# PCB-CMB-6.net
KiCad netlist of a schematic drawn in EAGLE
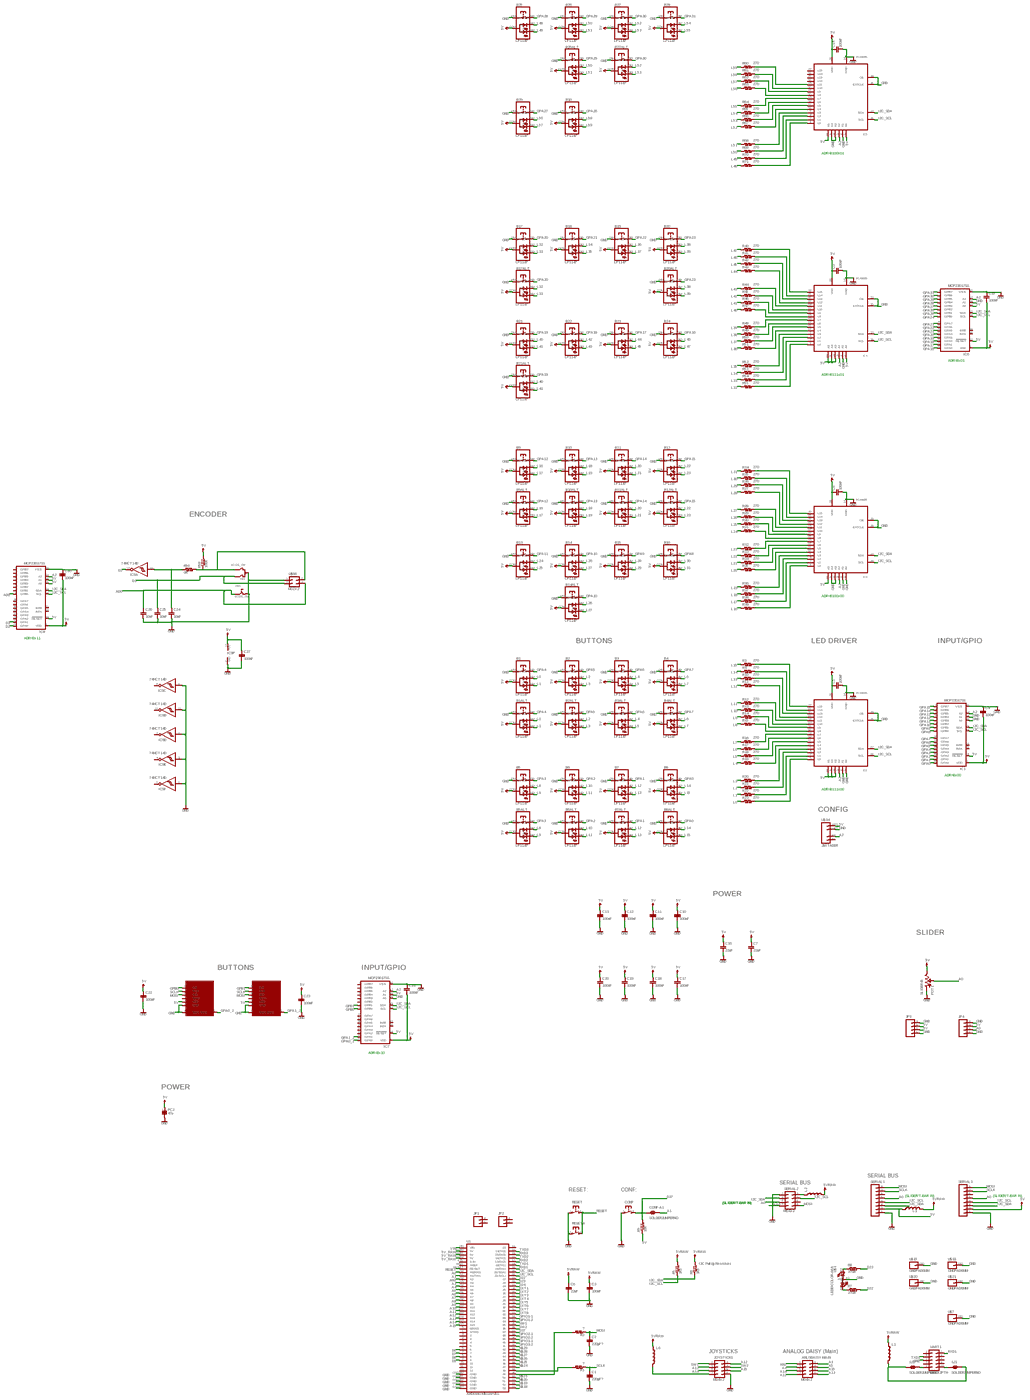
[diagram p0: schematic, sheet 1, overview]
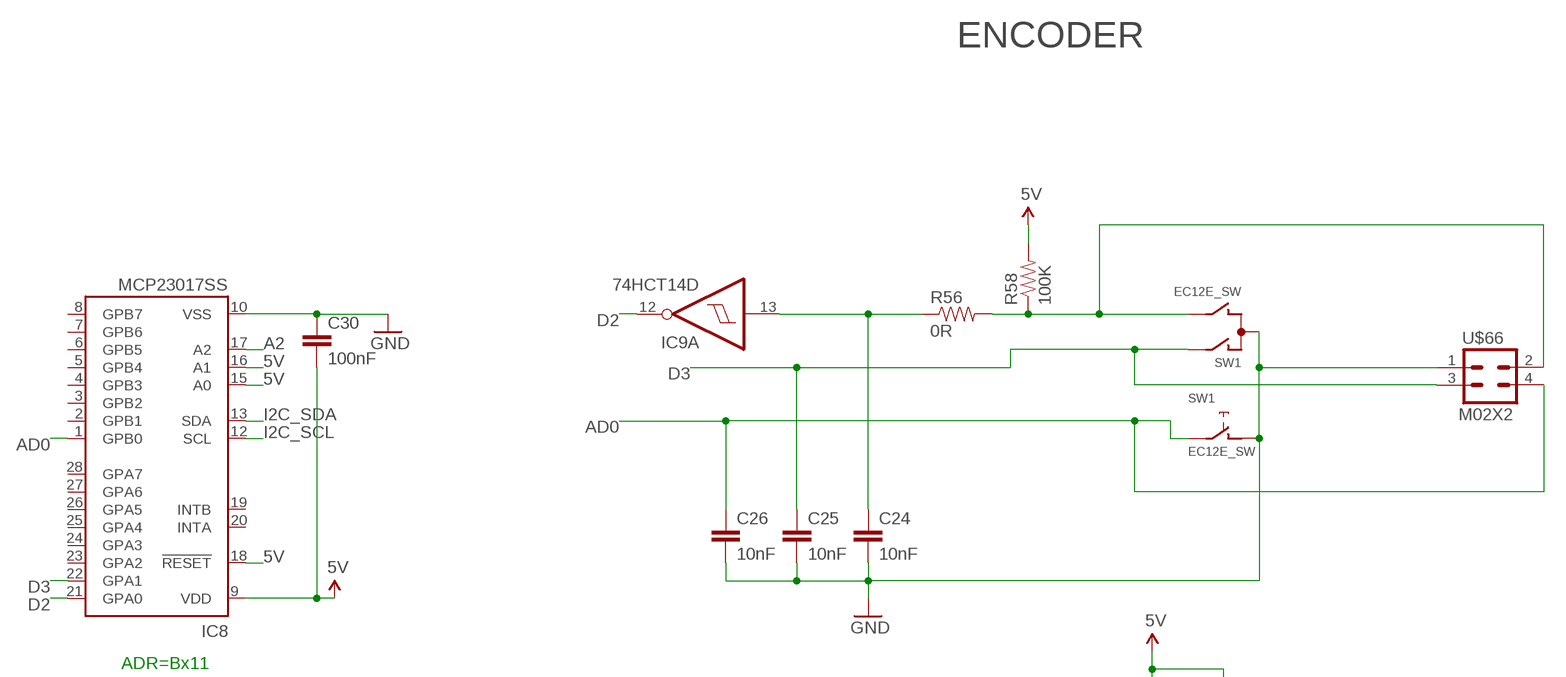
[diagram p1: schematic, sheet 1, part 1 of 6]
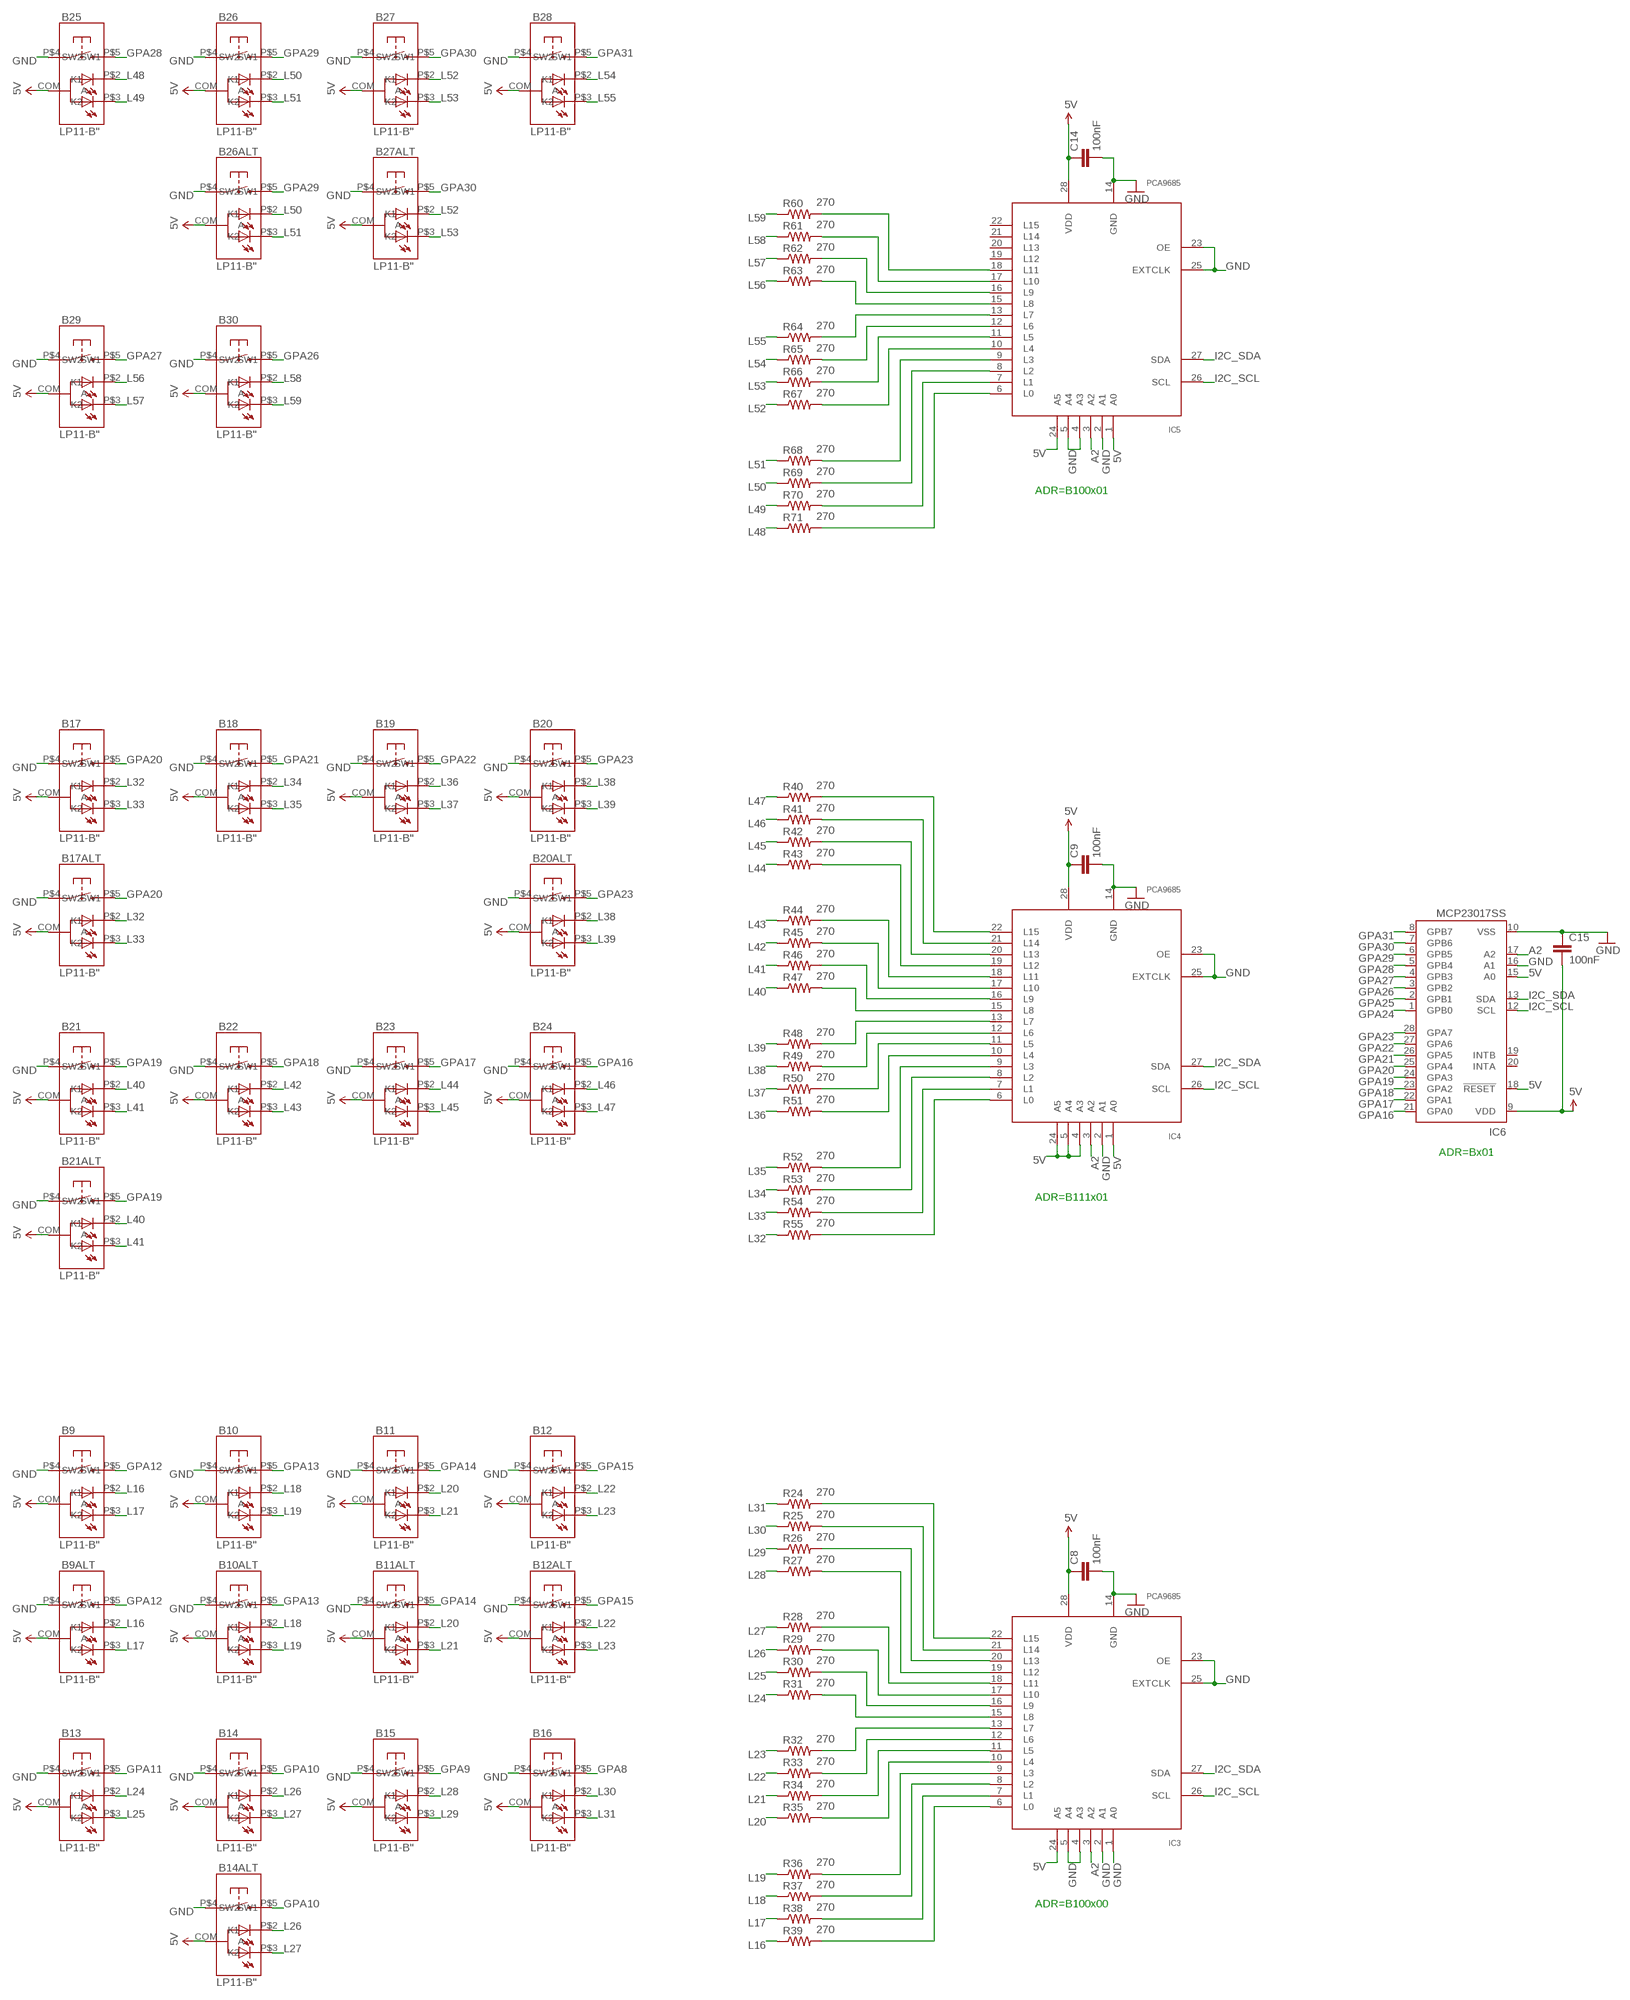
[diagram p2: schematic, sheet 1, part 2 of 6]
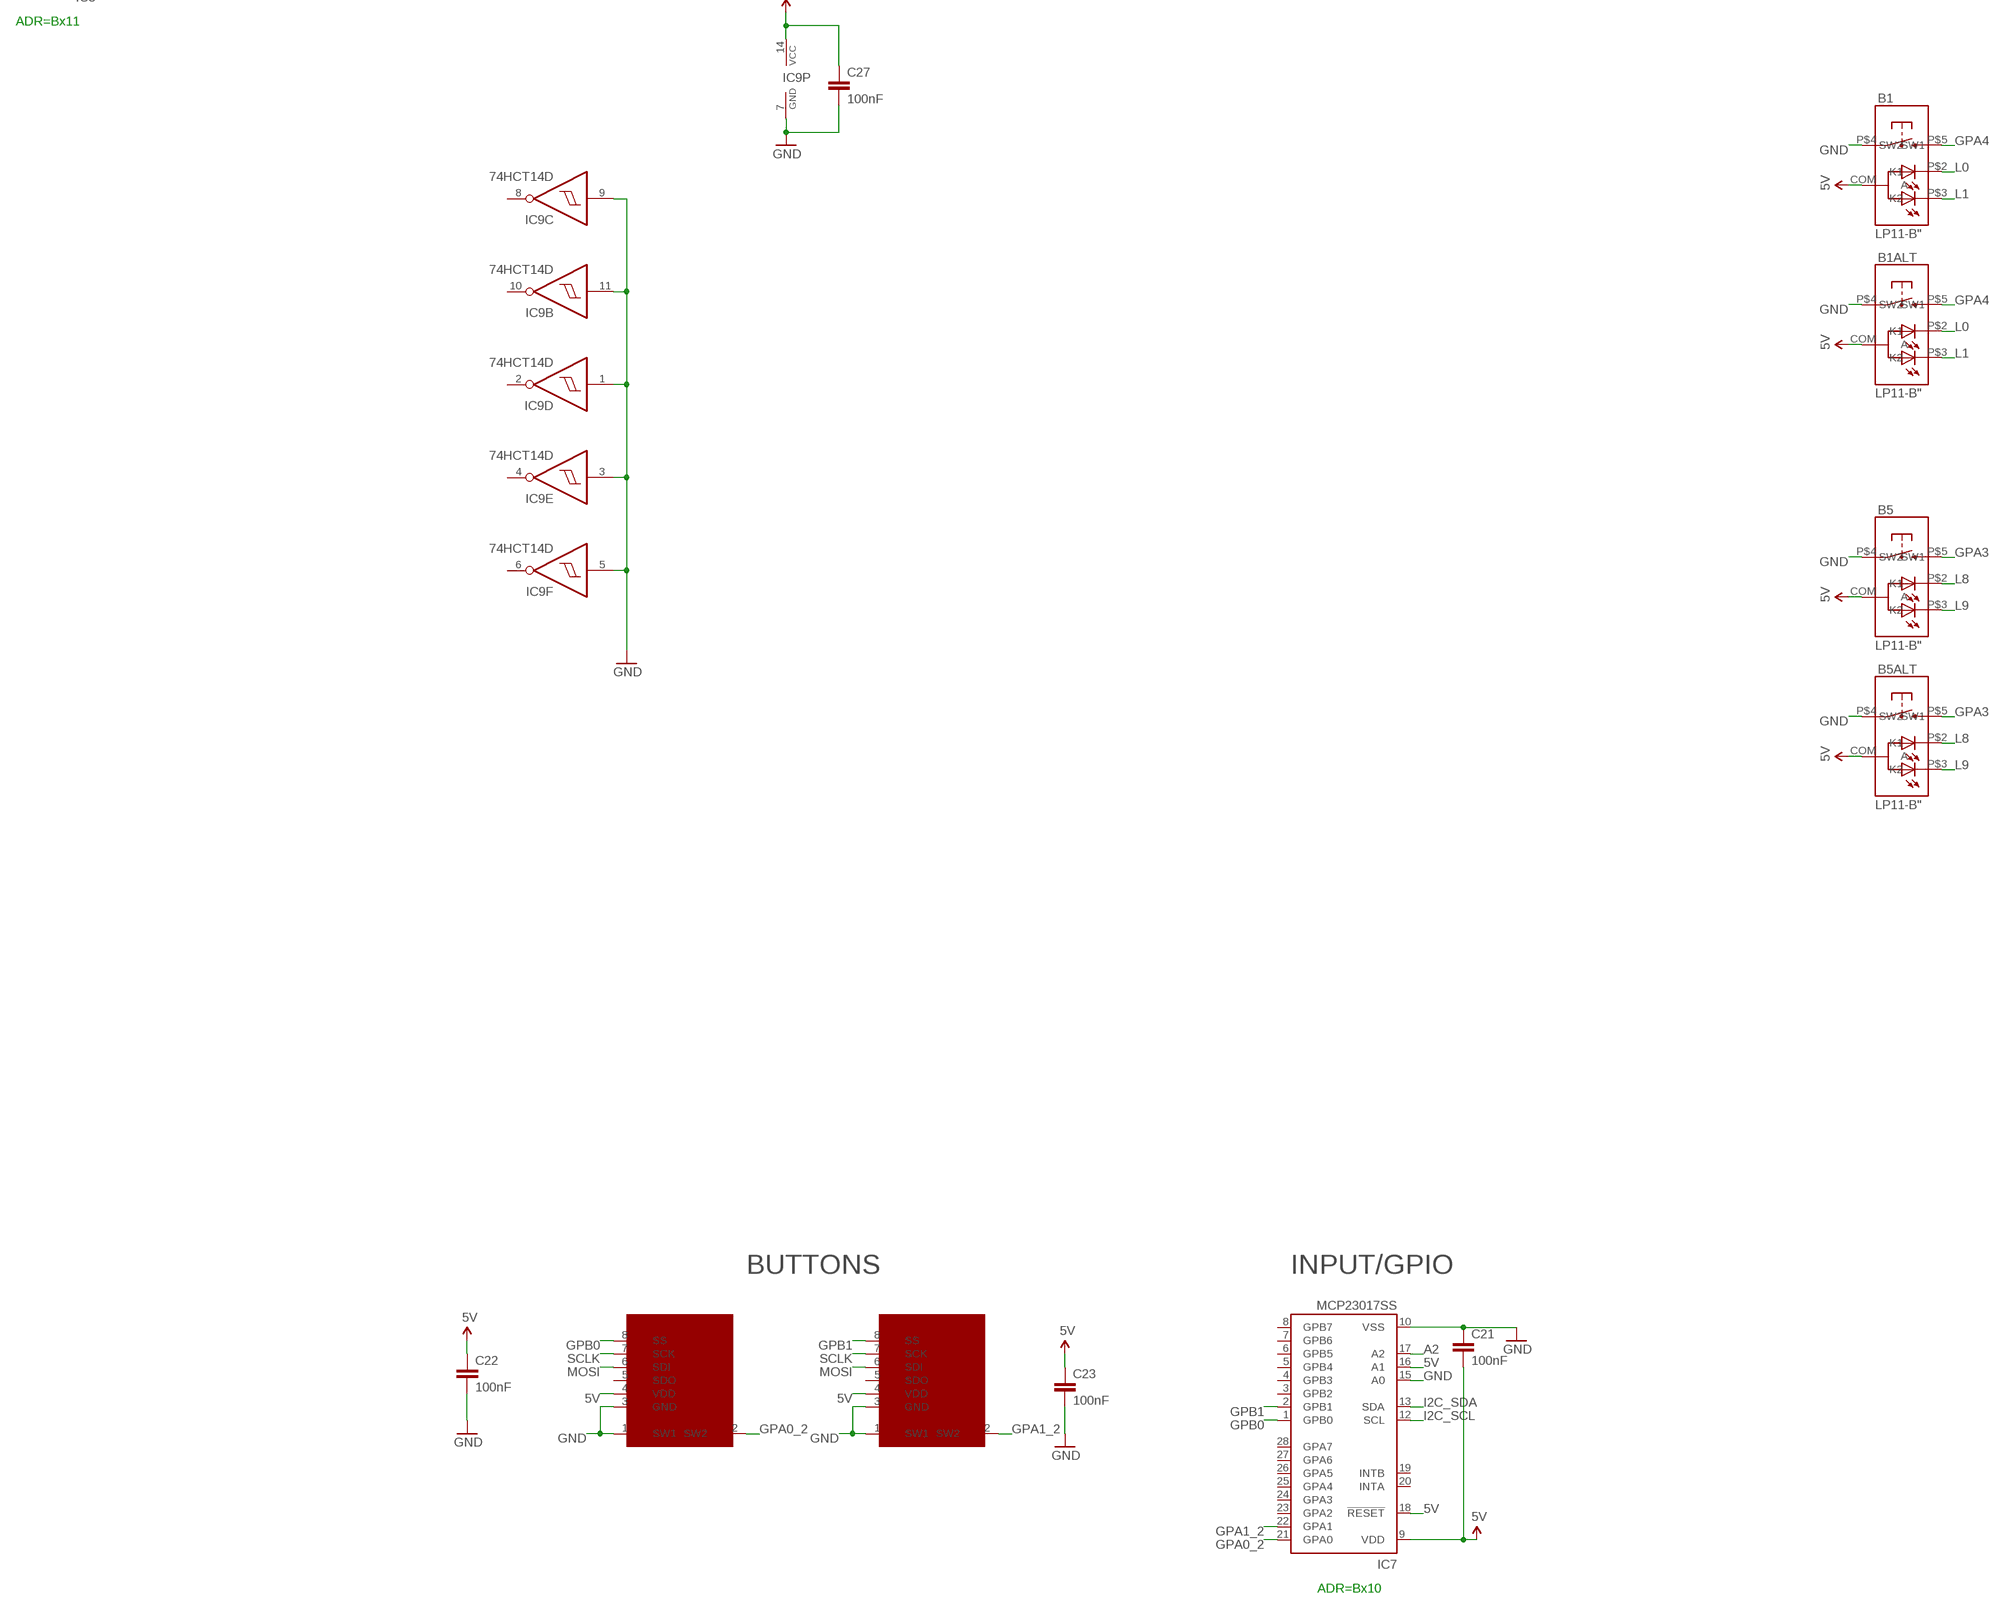
[diagram p3: schematic, sheet 1, part 3 of 6]
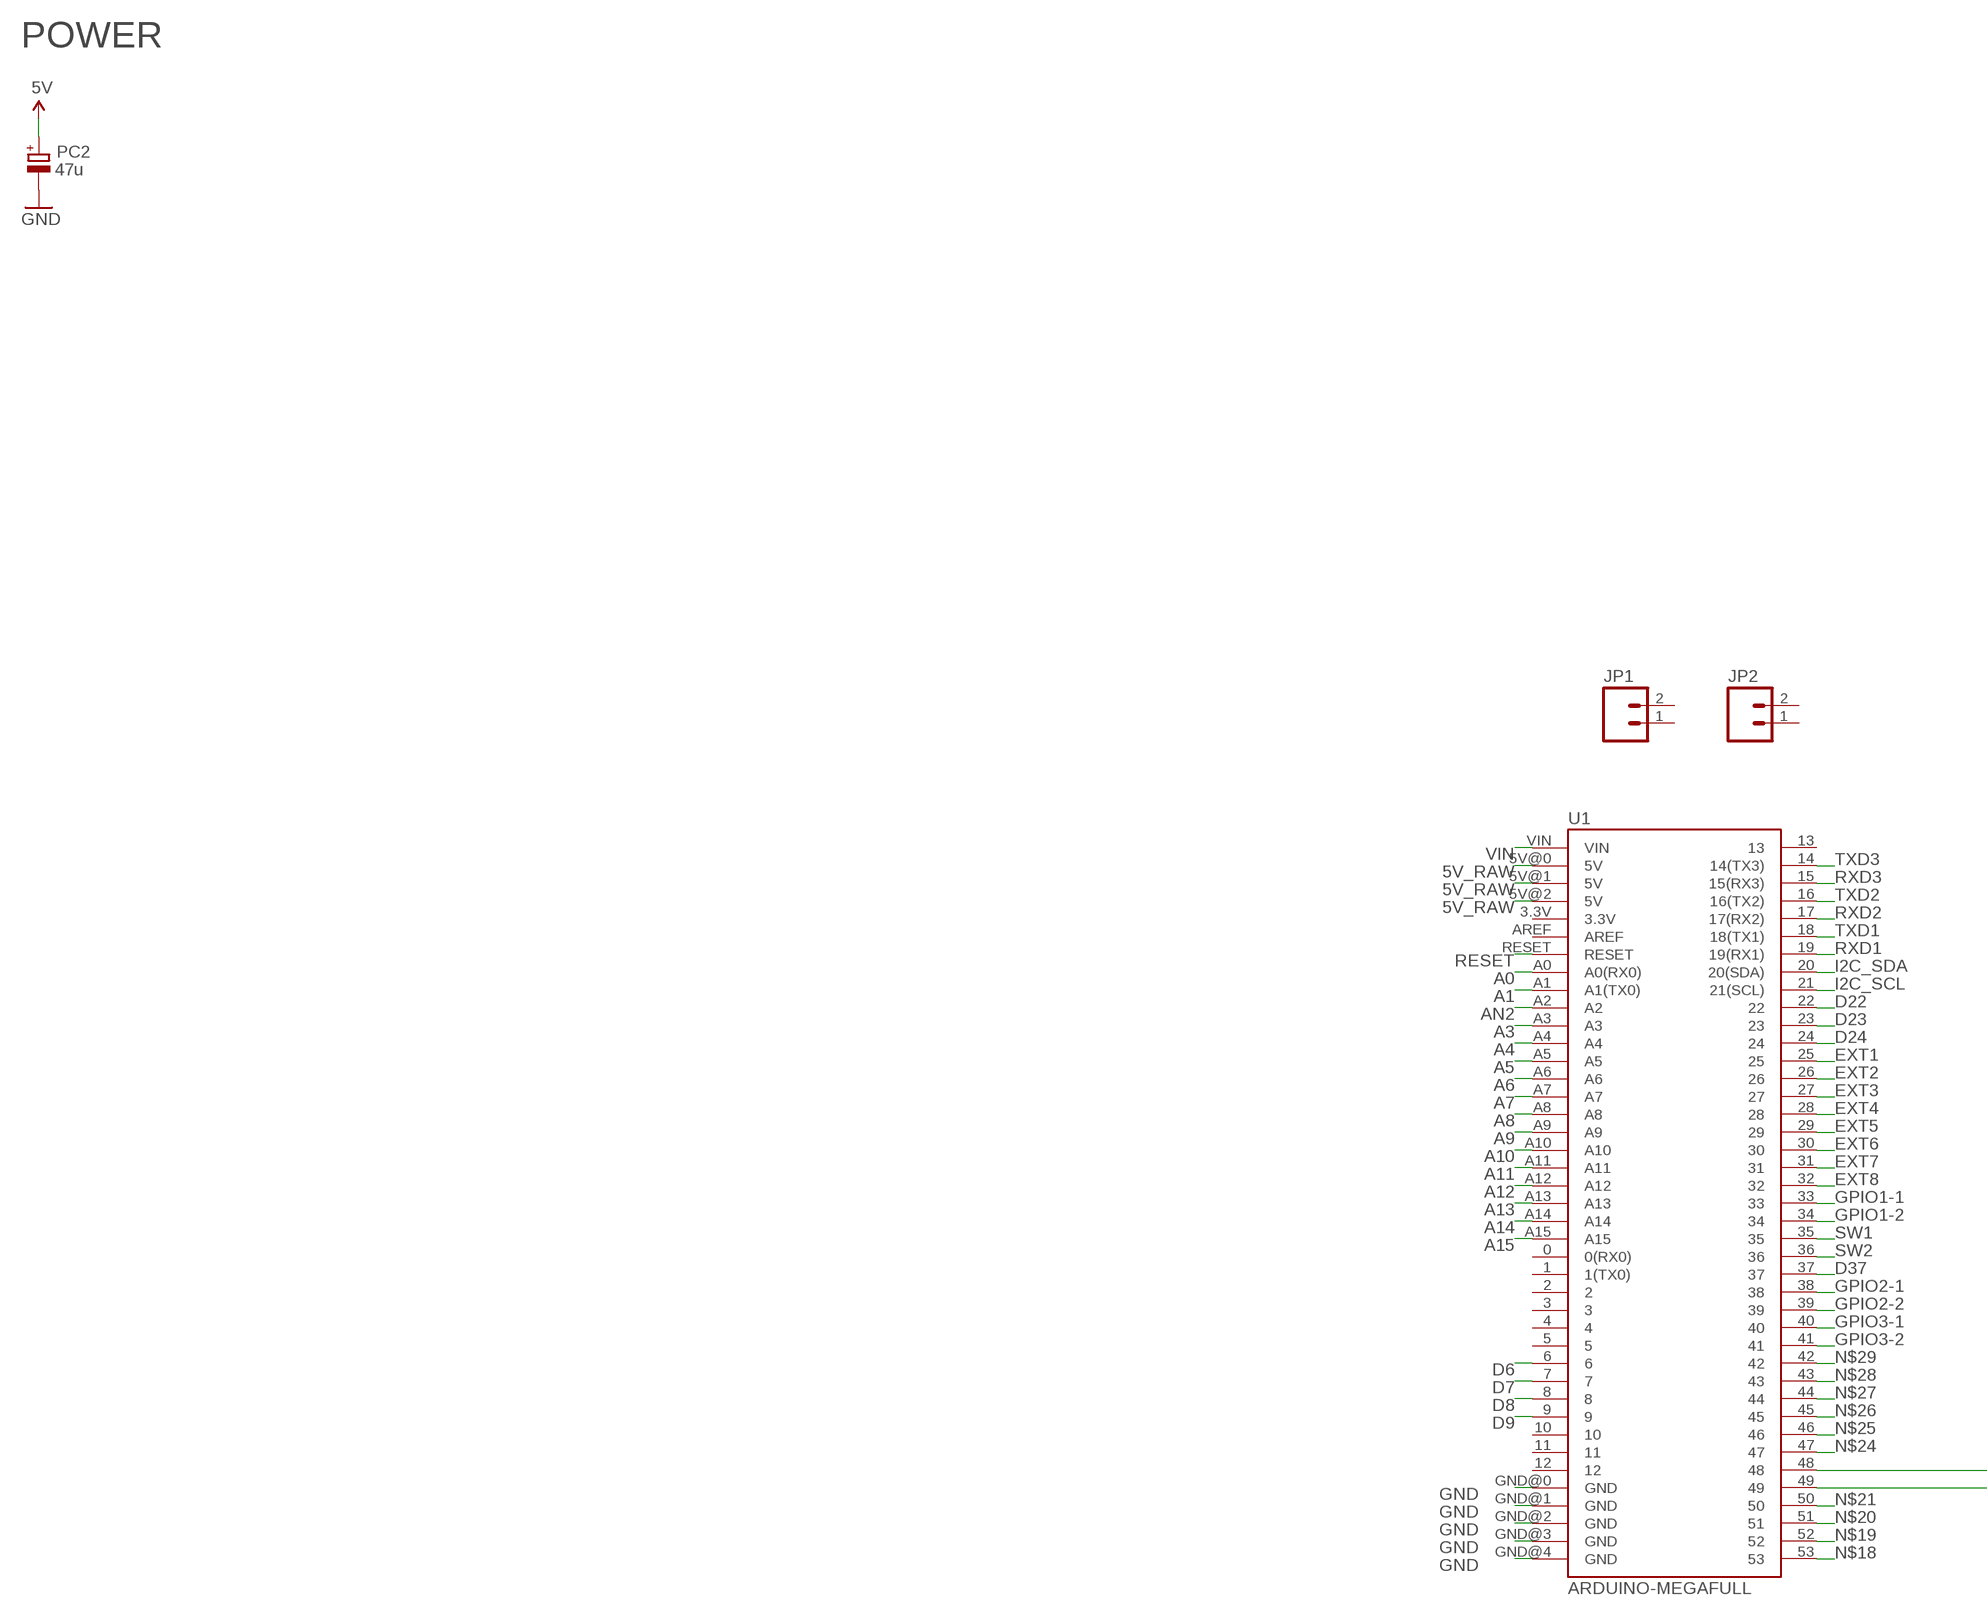
[diagram p4: schematic, sheet 1, part 4 of 6]
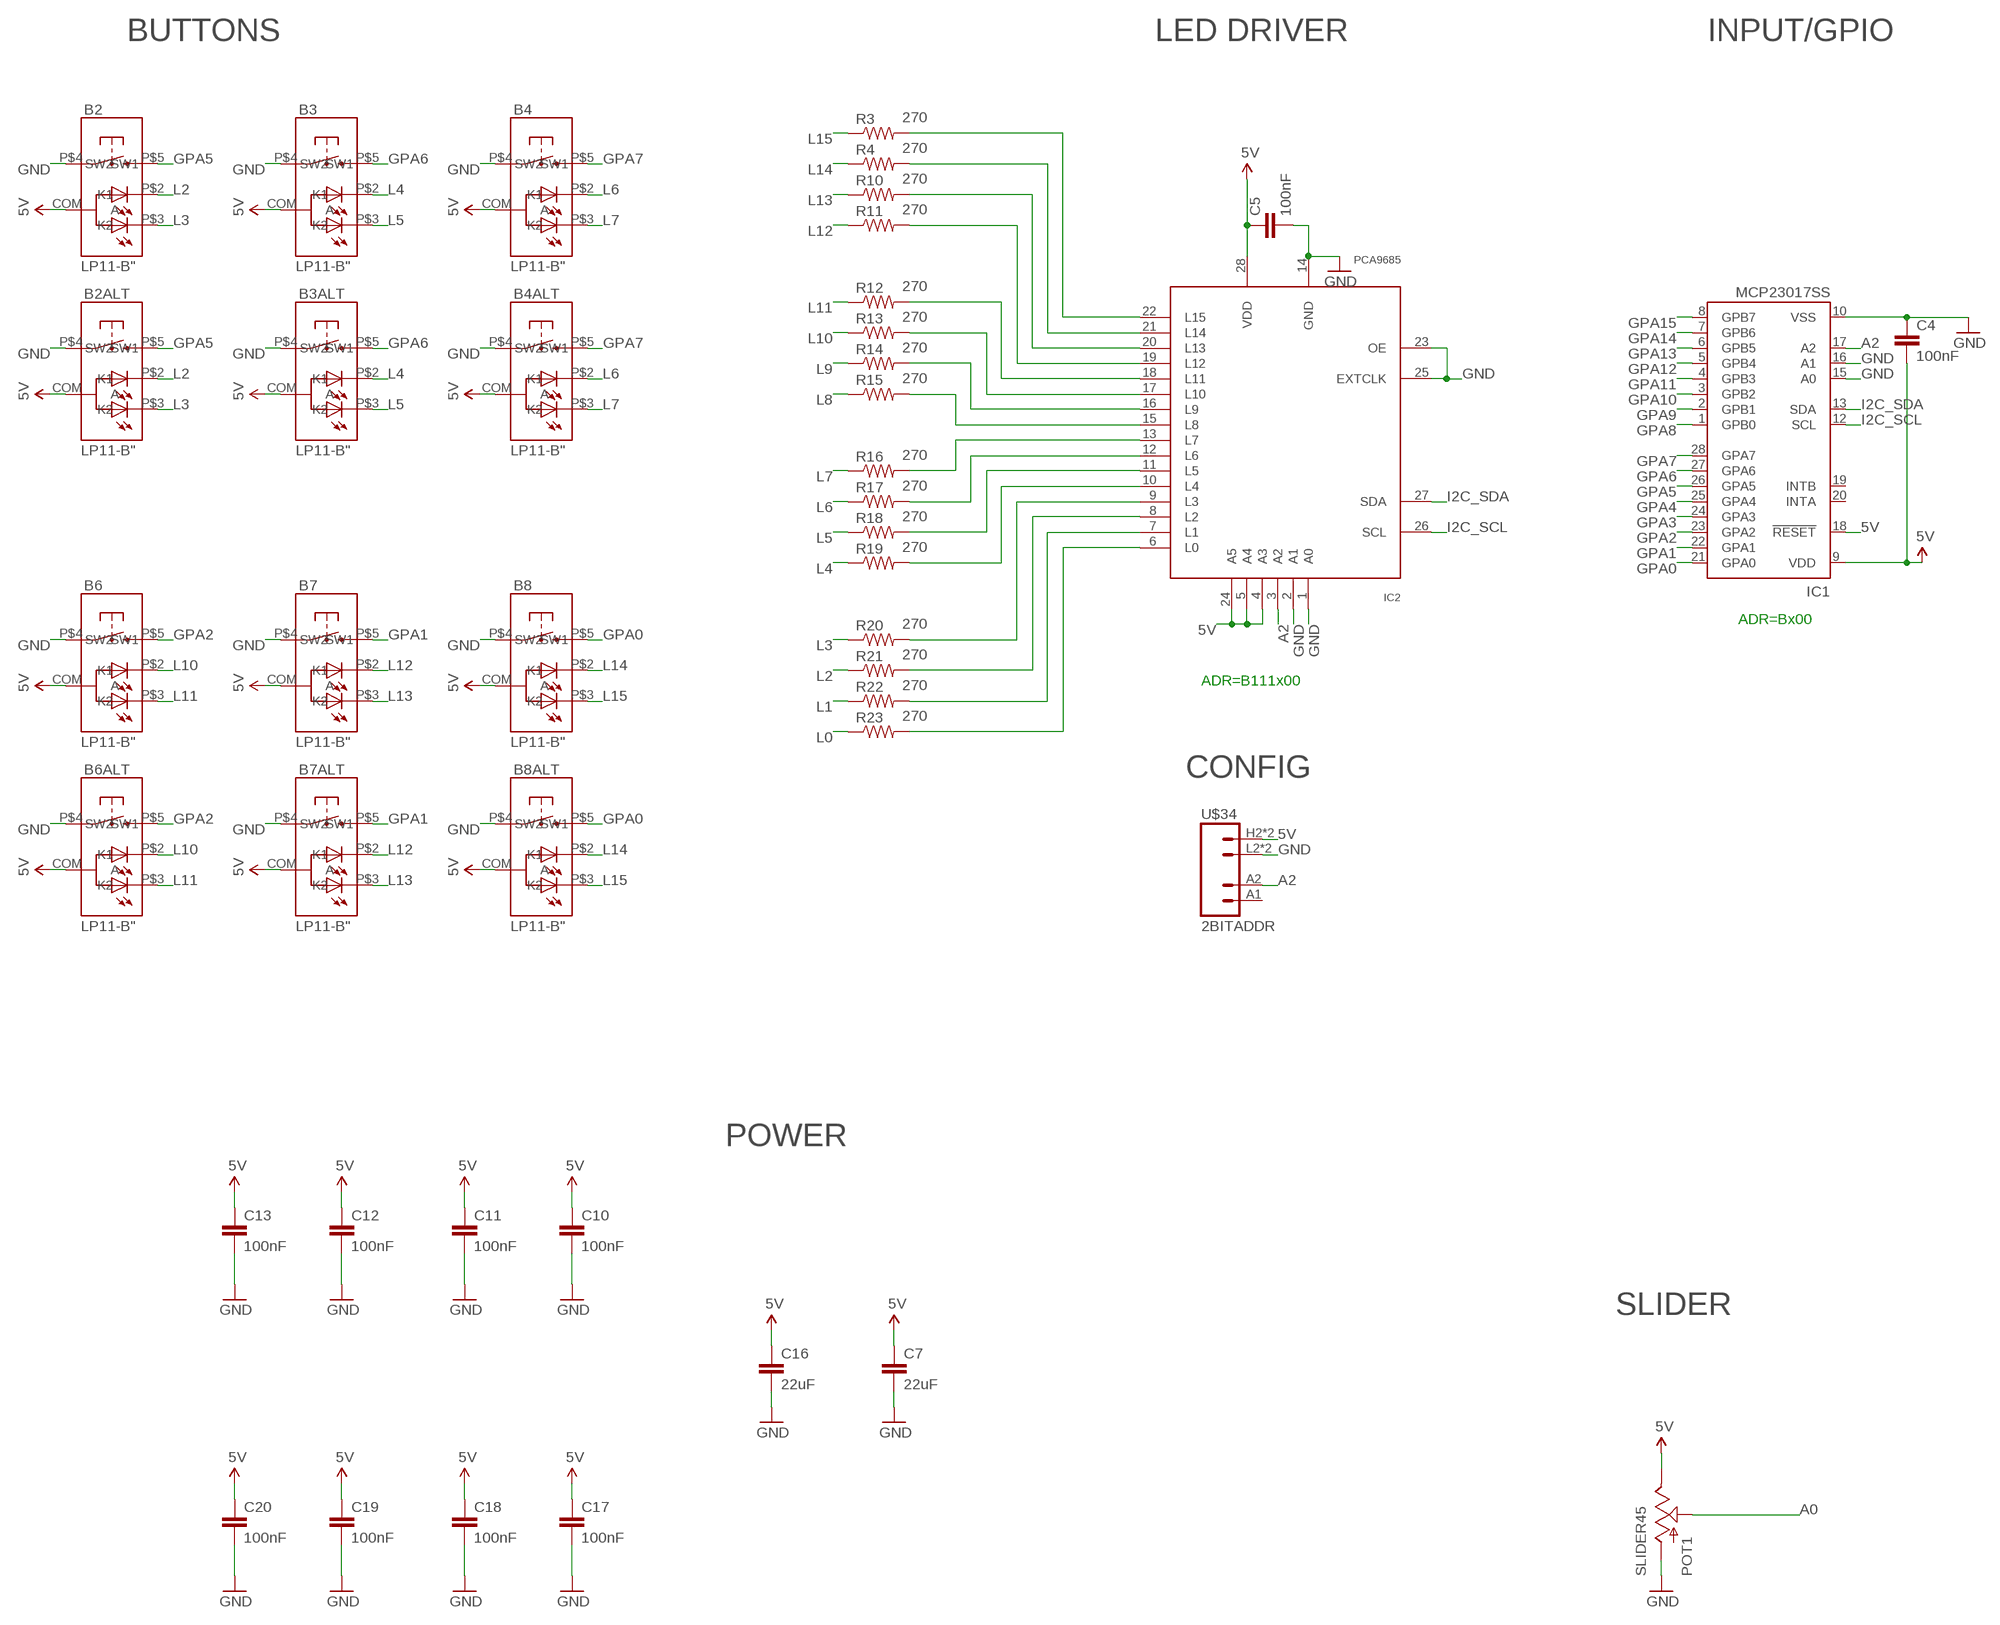
[diagram p5: schematic, sheet 1, part 5 of 6]
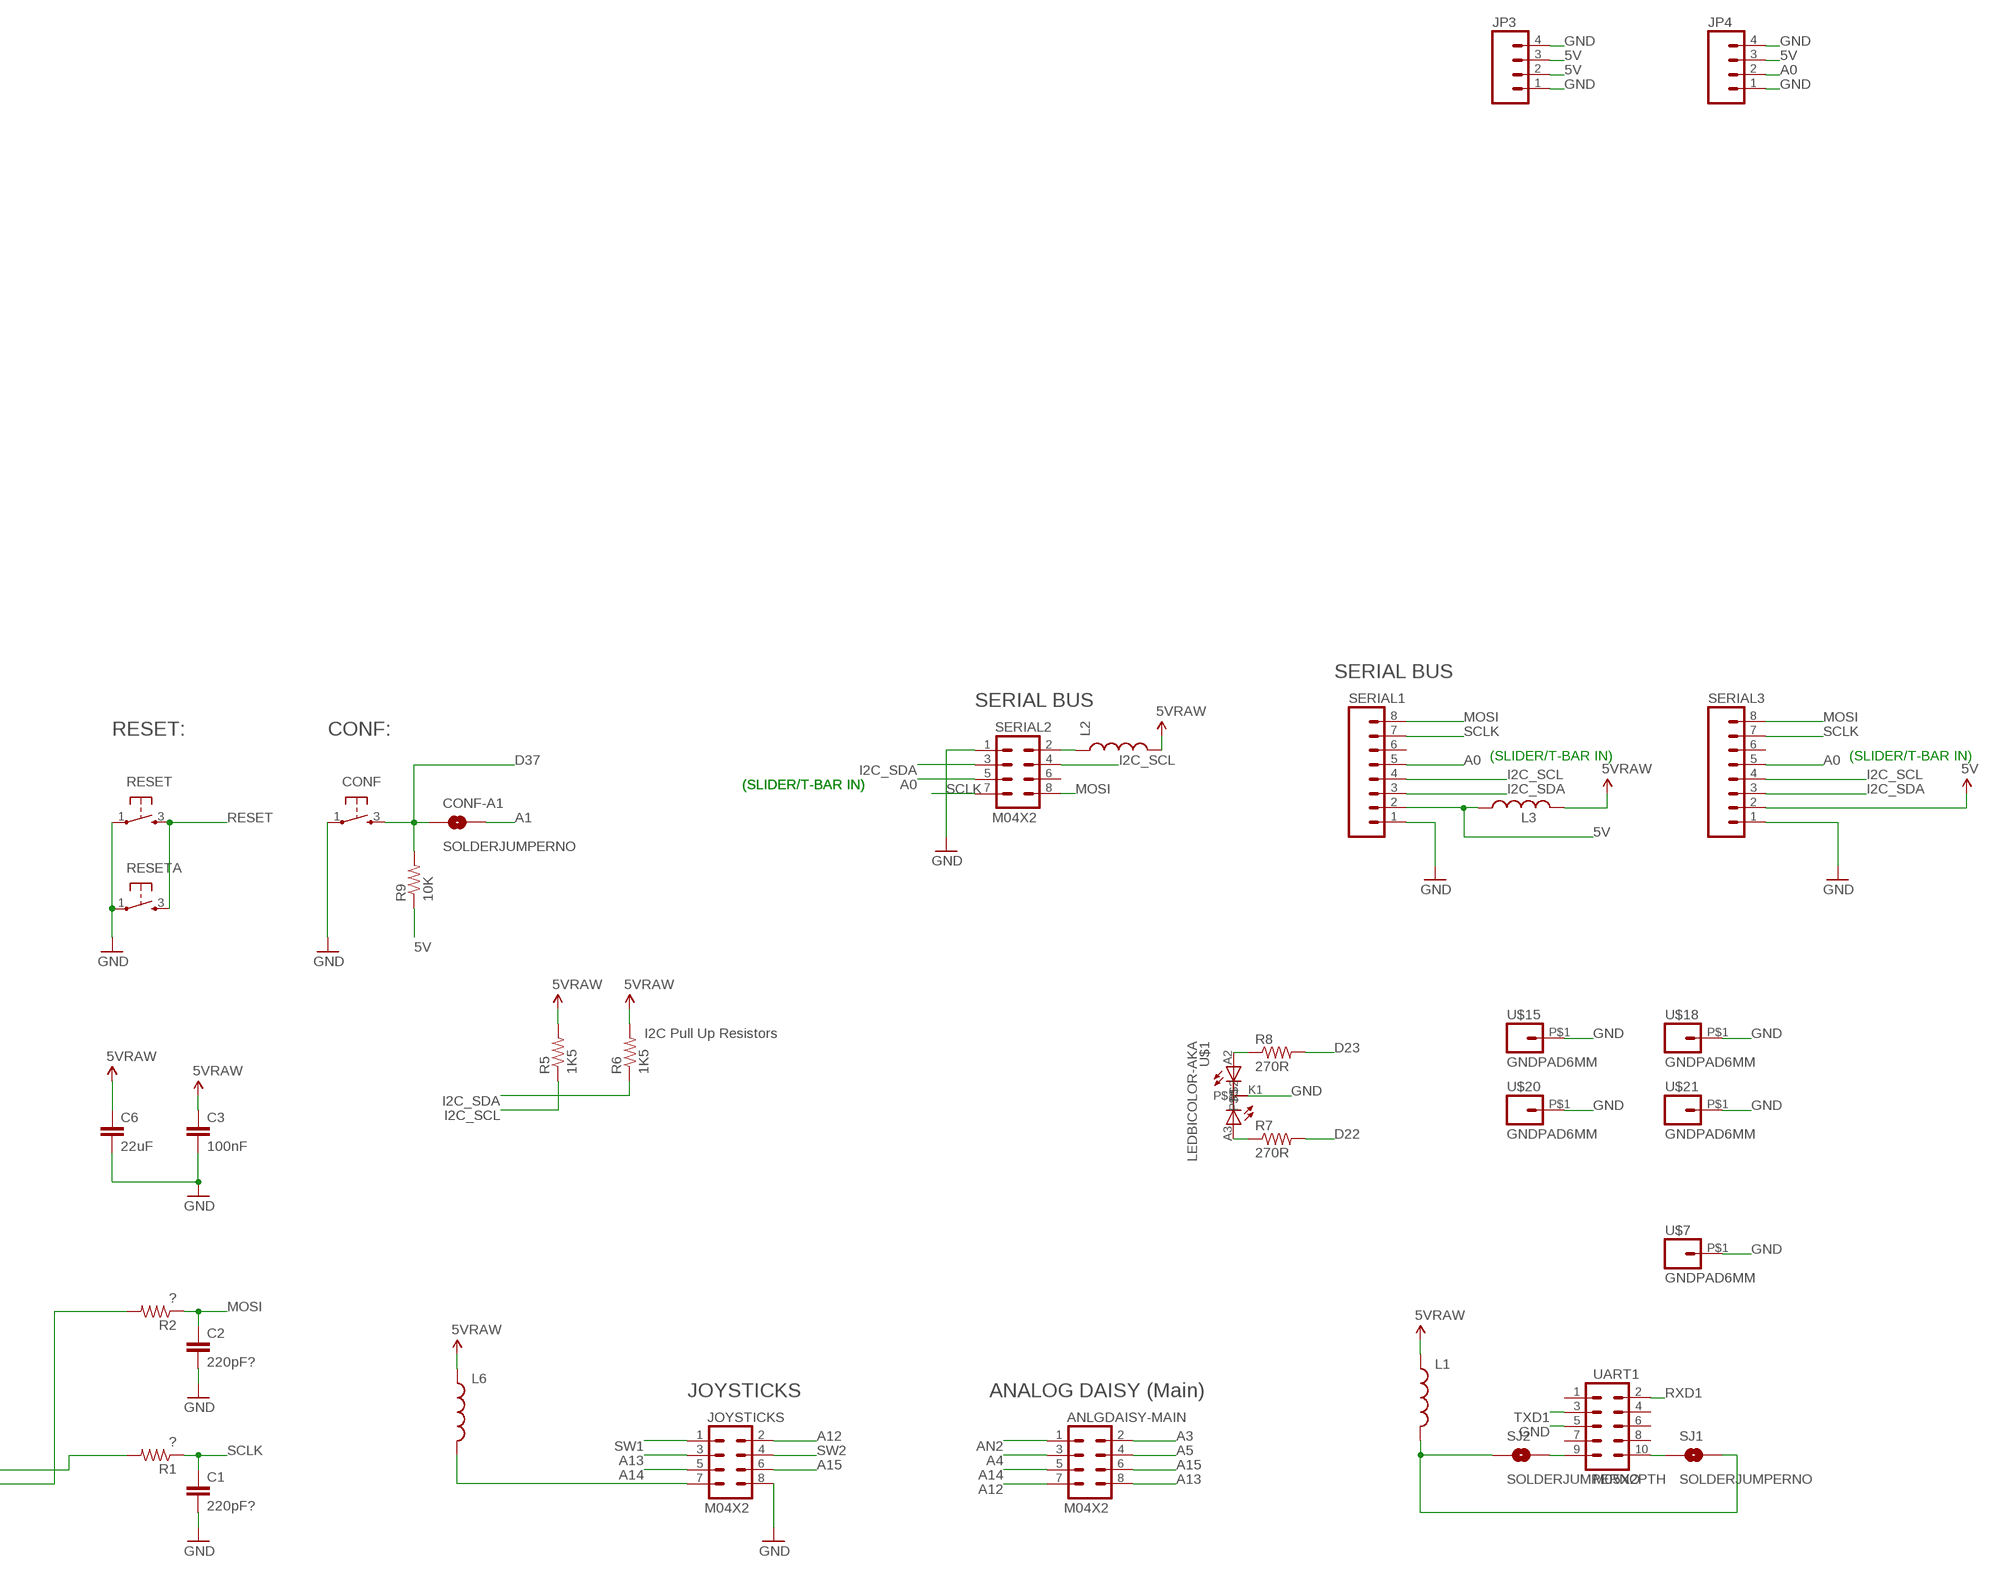
[diagram p6: schematic, sheet 1, part 6 of 6]

(export (version "E")
  (design (tool "Eeschema 10.0.6"))
  (components
    (comp (ref "ANLGDAISY-MAIN")
      (value "M04X2")
      (footprint "eagle-import:2X4")
      (libsource (lib "eagle-import") (part "M04X2"))
    )
    (comp (ref "B1")
      (value "LP11-B\"")
      (footprint "eagle-import:LP11")
      (libsource (lib "eagle-import") (part "LP11-B{dblquote}"))
    )
    (comp (ref "B1ALT")
      (value "LP11-B\"")
      (footprint "eagle-import:LP11")
      (libsource (lib "eagle-import") (part "LP11-B{dblquote}"))
    )
    (comp (ref "B2")
      (value "LP11-B\"")
      (footprint "eagle-import:LP11")
      (libsource (lib "eagle-import") (part "LP11-B{dblquote}"))
    )
    (comp (ref "B2ALT")
      (value "LP11-B\"")
      (footprint "eagle-import:LP11")
      (libsource (lib "eagle-import") (part "LP11-B{dblquote}"))
    )
    (comp (ref "B3")
      (value "LP11-B\"")
      (footprint "eagle-import:LP11")
      (libsource (lib "eagle-import") (part "LP11-B{dblquote}"))
    )
    (comp (ref "B3ALT")
      (value "LP11-B\"")
      (footprint "eagle-import:LP11")
      (libsource (lib "eagle-import") (part "LP11-B{dblquote}"))
    )
    (comp (ref "B4")
      (value "LP11-B\"")
      (footprint "eagle-import:LP11")
      (libsource (lib "eagle-import") (part "LP11-B{dblquote}"))
    )
    (comp (ref "B4ALT")
      (value "LP11-B\"")
      (footprint "eagle-import:LP11")
      (libsource (lib "eagle-import") (part "LP11-B{dblquote}"))
    )
    (comp (ref "B5")
      (value "LP11-B\"")
      (footprint "eagle-import:LP11")
      (libsource (lib "eagle-import") (part "LP11-B{dblquote}"))
    )
    (comp (ref "B5ALT")
      (value "LP11-B\"")
      (footprint "eagle-import:LP11")
      (libsource (lib "eagle-import") (part "LP11-B{dblquote}"))
    )
    (comp (ref "B6")
      (value "LP11-B\"")
      (footprint "eagle-import:LP11")
      (libsource (lib "eagle-import") (part "LP11-B{dblquote}"))
    )
    (comp (ref "B6ALT")
      (value "LP11-B\"")
      (footprint "eagle-import:LP11")
      (libsource (lib "eagle-import") (part "LP11-B{dblquote}"))
    )
    (comp (ref "B7")
      (value "LP11-B\"")
      (footprint "eagle-import:LP11")
      (libsource (lib "eagle-import") (part "LP11-B{dblquote}"))
    )
    (comp (ref "B7ALT")
      (value "LP11-B\"")
      (footprint "eagle-import:LP11")
      (libsource (lib "eagle-import") (part "LP11-B{dblquote}"))
    )
    (comp (ref "B8")
      (value "LP11-B\"")
      (footprint "eagle-import:LP11")
      (libsource (lib "eagle-import") (part "LP11-B{dblquote}"))
    )
    (comp (ref "B8ALT")
      (value "LP11-B\"")
      (footprint "eagle-import:LP11")
      (libsource (lib "eagle-import") (part "LP11-B{dblquote}"))
    )
    (comp (ref "B9")
      (value "LP11-B\"")
      (footprint "eagle-import:LP11")
      (libsource (lib "eagle-import") (part "LP11-B{dblquote}"))
    )
    (comp (ref "B9ALT")
      (value "LP11-B\"")
      (footprint "eagle-import:LP11")
      (libsource (lib "eagle-import") (part "LP11-B{dblquote}"))
    )
    (comp (ref "B10")
      (value "LP11-B\"")
      (footprint "eagle-import:LP11")
      (libsource (lib "eagle-import") (part "LP11-B{dblquote}"))
    )
    (comp (ref "B10ALT")
      (value "LP11-B\"")
      (footprint "eagle-import:LP11")
      (libsource (lib "eagle-import") (part "LP11-B{dblquote}"))
    )
    (comp (ref "B11")
      (value "LP11-B\"")
      (footprint "eagle-import:LP11")
      (libsource (lib "eagle-import") (part "LP11-B{dblquote}"))
    )
    (comp (ref "B11ALT")
      (value "LP11-B\"")
      (footprint "eagle-import:LP11")
      (libsource (lib "eagle-import") (part "LP11-B{dblquote}"))
    )
    (comp (ref "B12")
      (value "LP11-B\"")
      (footprint "eagle-import:LP11")
      (libsource (lib "eagle-import") (part "LP11-B{dblquote}"))
    )
    (comp (ref "B12ALT")
      (value "LP11-B\"")
      (footprint "eagle-import:LP11")
      (libsource (lib "eagle-import") (part "LP11-B{dblquote}"))
    )
    (comp (ref "B13")
      (value "LP11-B\"")
      (footprint "eagle-import:LP11")
      (libsource (lib "eagle-import") (part "LP11-B{dblquote}"))
    )
    (comp (ref "B14")
      (value "LP11-B\"")
      (footprint "eagle-import:LP11")
      (libsource (lib "eagle-import") (part "LP11-B{dblquote}"))
    )
    (comp (ref "B14ALT")
      (value "LP11-B\"")
      (footprint "eagle-import:LP11")
      (libsource (lib "eagle-import") (part "LP11-B{dblquote}"))
    )
    (comp (ref "B15")
      (value "LP11-B\"")
      (footprint "eagle-import:LP11")
      (libsource (lib "eagle-import") (part "LP11-B{dblquote}"))
    )
    (comp (ref "B16")
      (value "LP11-B\"")
      (footprint "eagle-import:LP11")
      (libsource (lib "eagle-import") (part "LP11-B{dblquote}"))
    )
    (comp (ref "B17")
      (value "LP11-B\"")
      (footprint "eagle-import:LP11")
      (libsource (lib "eagle-import") (part "LP11-B{dblquote}"))
    )
    (comp (ref "B17ALT")
      (value "LP11-B\"")
      (footprint "eagle-import:LP11")
      (libsource (lib "eagle-import") (part "LP11-B{dblquote}"))
    )
    (comp (ref "B18")
      (value "LP11-B\"")
      (footprint "eagle-import:LP11")
      (libsource (lib "eagle-import") (part "LP11-B{dblquote}"))
    )
    (comp (ref "B19")
      (value "LP11-B\"")
      (footprint "eagle-import:LP11")
      (libsource (lib "eagle-import") (part "LP11-B{dblquote}"))
    )
    (comp (ref "B20")
      (value "LP11-B\"")
      (footprint "eagle-import:LP11")
      (libsource (lib "eagle-import") (part "LP11-B{dblquote}"))
    )
    (comp (ref "B20ALT")
      (value "LP11-B\"")
      (footprint "eagle-import:LP11")
      (libsource (lib "eagle-import") (part "LP11-B{dblquote}"))
    )
    (comp (ref "B21")
      (value "LP11-B\"")
      (footprint "eagle-import:LP11")
      (libsource (lib "eagle-import") (part "LP11-B{dblquote}"))
    )
    (comp (ref "B21ALT")
      (value "LP11-B\"")
      (footprint "eagle-import:LP11")
      (libsource (lib "eagle-import") (part "LP11-B{dblquote}"))
    )
    (comp (ref "B22")
      (value "LP11-B\"")
      (footprint "eagle-import:LP11")
      (libsource (lib "eagle-import") (part "LP11-B{dblquote}"))
    )
    (comp (ref "B23")
      (value "LP11-B\"")
      (footprint "eagle-import:LP11")
      (libsource (lib "eagle-import") (part "LP11-B{dblquote}"))
    )
    (comp (ref "B24")
      (value "LP11-B\"")
      (footprint "eagle-import:LP11")
      (libsource (lib "eagle-import") (part "LP11-B{dblquote}"))
    )
    (comp (ref "B25")
      (value "LP11-B\"")
      (footprint "eagle-import:LP11")
      (libsource (lib "eagle-import") (part "LP11-B{dblquote}"))
    )
    (comp (ref "B26")
      (value "LP11-B\"")
      (footprint "eagle-import:LP11")
      (libsource (lib "eagle-import") (part "LP11-B{dblquote}"))
    )
    (comp (ref "B26ALT")
      (value "LP11-B\"")
      (footprint "eagle-import:LP11")
      (libsource (lib "eagle-import") (part "LP11-B{dblquote}"))
    )
    (comp (ref "B27")
      (value "LP11-B\"")
      (footprint "eagle-import:LP11")
      (libsource (lib "eagle-import") (part "LP11-B{dblquote}"))
    )
    (comp (ref "B27ALT")
      (value "LP11-B\"")
      (footprint "eagle-import:LP11")
      (libsource (lib "eagle-import") (part "LP11-B{dblquote}"))
    )
    (comp (ref "B28")
      (value "LP11-B\"")
      (footprint "eagle-import:LP11")
      (libsource (lib "eagle-import") (part "LP11-B{dblquote}"))
    )
    (comp (ref "B29")
      (value "LP11-B\"")
      (footprint "eagle-import:LP11")
      (libsource (lib "eagle-import") (part "LP11-B{dblquote}"))
    )
    (comp (ref "B30")
      (value "LP11-B\"")
      (footprint "eagle-import:LP11")
      (libsource (lib "eagle-import") (part "LP11-B{dblquote}"))
    )
    (comp (ref "C1")
      (value "220pF?")
      (footprint "eagle-import:0603-CAP")
      (libsource (lib "eagle-import") (part "CAP0603-CAP"))
    )
    (comp (ref "C2")
      (value "220pF?")
      (footprint "eagle-import:0603-CAP")
      (libsource (lib "eagle-import") (part "CAP0603-CAP"))
    )
    (comp (ref "C3")
      (value "100nF")
      (footprint "eagle-import:0603-CAP")
      (libsource (lib "eagle-import") (part "CAP0603-CAP"))
    )
    (comp (ref "C4")
      (value "100nF")
      (footprint "eagle-import:0603-CAP")
      (libsource (lib "eagle-import") (part "CAP0603-CAP"))
    )
    (comp (ref "C5")
      (value "100nF")
      (footprint "eagle-import:0603-CAP")
      (libsource (lib "eagle-import") (part "CAP0603-CAP"))
    )
    (comp (ref "C6")
      (value "22uF")
      (footprint "eagle-import:0805")
      (libsource (lib "eagle-import") (part "CAP0805"))
    )
    (comp (ref "C7")
      (value "22uF")
      (footprint "eagle-import:0805")
      (libsource (lib "eagle-import") (part "CAP0805"))
    )
    (comp (ref "C8")
      (value "100nF")
      (footprint "eagle-import:0603-CAP")
      (libsource (lib "eagle-import") (part "CAP0603-CAP"))
    )
    (comp (ref "C9")
      (value "100nF")
      (footprint "eagle-import:0603-CAP")
      (libsource (lib "eagle-import") (part "CAP0603-CAP"))
    )
    (comp (ref "C10")
      (value "100nF")
      (footprint "eagle-import:0603-CAP")
      (libsource (lib "eagle-import") (part "CAP0603-CAP"))
    )
    (comp (ref "C11")
      (value "100nF")
      (footprint "eagle-import:0603-CAP")
      (libsource (lib "eagle-import") (part "CAP0603-CAP"))
    )
    (comp (ref "C12")
      (value "100nF")
      (footprint "eagle-import:0603-CAP")
      (libsource (lib "eagle-import") (part "CAP0603-CAP"))
    )
    (comp (ref "C13")
      (value "100nF")
      (footprint "eagle-import:0603-CAP")
      (libsource (lib "eagle-import") (part "CAP0603-CAP"))
    )
    (comp (ref "C14")
      (value "100nF")
      (footprint "eagle-import:0603-CAP")
      (libsource (lib "eagle-import") (part "CAP0603-CAP"))
    )
    (comp (ref "C15")
      (value "100nF")
      (footprint "eagle-import:0603-CAP")
      (libsource (lib "eagle-import") (part "CAP0603-CAP"))
    )
    (comp (ref "C16")
      (value "22uF")
      (footprint "eagle-import:0805")
      (libsource (lib "eagle-import") (part "CAP0805"))
    )
    (comp (ref "C17")
      (value "100nF")
      (footprint "eagle-import:0603-CAP")
      (libsource (lib "eagle-import") (part "CAP0603-CAP"))
    )
    (comp (ref "C18")
      (value "100nF")
      (footprint "eagle-import:0603-CAP")
      (libsource (lib "eagle-import") (part "CAP0603-CAP"))
    )
    (comp (ref "C19")
      (value "100nF")
      (footprint "eagle-import:0603-CAP")
      (libsource (lib "eagle-import") (part "CAP0603-CAP"))
    )
    (comp (ref "C20")
      (value "100nF")
      (footprint "eagle-import:0603-CAP")
      (libsource (lib "eagle-import") (part "CAP0603-CAP"))
    )
    (comp (ref "C21")
      (value "100nF")
      (footprint "eagle-import:0603-CAP")
      (libsource (lib "eagle-import") (part "CAP0603-CAP"))
    )
    (comp (ref "C22")
      (value "100nF")
      (footprint "eagle-import:0603-CAP")
      (libsource (lib "eagle-import") (part "CAP0603-CAP"))
    )
    (comp (ref "C23")
      (value "100nF")
      (footprint "eagle-import:0603-CAP")
      (libsource (lib "eagle-import") (part "CAP0603-CAP"))
    )
    (comp (ref "C24")
      (value "10nF")
      (footprint "eagle-import:0603-CAP")
      (libsource (lib "eagle-import") (part "CAP0603-CAP"))
    )
    (comp (ref "C25")
      (value "10nF")
      (footprint "eagle-import:0603-CAP")
      (libsource (lib "eagle-import") (part "CAP0603-CAP"))
    )
    (comp (ref "C26")
      (value "10nF")
      (footprint "eagle-import:0603-CAP")
      (libsource (lib "eagle-import") (part "CAP0603-CAP"))
    )
    (comp (ref "C27")
      (value "100nF")
      (footprint "eagle-import:0603-CAP")
      (libsource (lib "eagle-import") (part "CAP0603-CAP"))
    )
    (comp (ref "C30")
      (value "100nF")
      (footprint "eagle-import:0603-CAP")
      (libsource (lib "eagle-import") (part "CAP0603-CAP"))
    )
    (comp (ref "CONF")
      (value "TAC_SWITCH")
      (footprint "eagle-import:PUSHBUTTON")
      (libsource (lib "eagle-import") (part "TAC_SWITCH"))
    )
    (comp (ref "CONF-A1")
      (value "SOLDERJUMPERNO")
      (footprint "eagle-import:SJ_2S-NO")
      (libsource (lib "eagle-import") (part "SOLDERJUMPERNO"))
    )
    (comp (ref "IC1")
      (value "MCP23017SS")
      (footprint "eagle-import:SSOP28")
      (fields
        (field (name "MF") "MICROCHIP")
        (field (name "MPN") "MCP23017-E/SS")
        (field (name "MPN_1") "MCP23017-E/SS")
        (field (name "OC_FARNELL") "1467674")
        (field (name "OC_NEWARK") "31K2960")
      )
      (libsource (lib "eagle-import") (part "MCP23017SS"))
    )
    (comp (ref "IC2")
      (value "PCA9685")
      (footprint "eagle-import:TSSOP28")
      (libsource (lib "eagle-import") (part "PCA9685"))
    )
    (comp (ref "IC3")
      (value "PCA9685")
      (footprint "eagle-import:TSSOP28")
      (libsource (lib "eagle-import") (part "PCA9685"))
    )
    (comp (ref "IC4")
      (value "PCA9685")
      (footprint "eagle-import:TSSOP28")
      (libsource (lib "eagle-import") (part "PCA9685"))
    )
    (comp (ref "IC5")
      (value "PCA9685")
      (footprint "eagle-import:TSSOP28")
      (libsource (lib "eagle-import") (part "PCA9685"))
    )
    (comp (ref "IC6")
      (value "MCP23017SS")
      (footprint "eagle-import:SSOP28")
      (fields
        (field (name "MF") "MICROCHIP")
        (field (name "MPN") "MCP23017-E/SS")
        (field (name "MPN_1") "MCP23017-E/SS")
        (field (name "OC_FARNELL") "1467674")
        (field (name "OC_NEWARK") "31K2960")
      )
      (libsource (lib "eagle-import") (part "MCP23017SS"))
    )
    (comp (ref "IC7")
      (value "MCP23017SS")
      (footprint "eagle-import:SSOP28")
      (fields
        (field (name "MF") "MICROCHIP")
        (field (name "MPN") "MCP23017-E/SS")
        (field (name "MPN_1") "MCP23017-E/SS")
        (field (name "OC_FARNELL") "1467674")
        (field (name "OC_NEWARK") "31K2960")
      )
      (libsource (lib "eagle-import") (part "MCP23017SS"))
    )
    (comp (ref "IC8")
      (value "MCP23017SS")
      (footprint "eagle-import:SSOP28")
      (fields
        (field (name "MF") "MICROCHIP")
        (field (name "MPN") "MCP23017-E/SS")
        (field (name "MPN_1") "MCP23017-E/SS")
        (field (name "OC_FARNELL") "1467674")
        (field (name "OC_NEWARK") "31K2960")
      )
      (libsource (lib "eagle-import") (part "MCP23017SS"))
    )
    (comp (ref "IC9")
      (value "74HCT14D")
      (footprint "eagle-import:SO14")
      (libsource (lib "eagle-import") (part "7414DHCT"))
    )
    (comp (ref "JOYSTICKS")
      (value "M04X2")
      (footprint "eagle-import:2X4")
      (libsource (lib "eagle-import") (part "M04X2"))
    )
    (comp (ref "JP1")
      (value "M02PTH")
      (footprint "eagle-import:1X02")
      (libsource (lib "eagle-import") (part "M02PTH"))
    )
    (comp (ref "JP2")
      (value "M02PTH")
      (footprint "eagle-import:1X02")
      (libsource (lib "eagle-import") (part "M02PTH"))
    )
    (comp (ref "JP3")
      (value "M04PTH")
      (footprint "eagle-import:1X04")
      (libsource (lib "eagle-import") (part "M04PTH"))
    )
    (comp (ref "JP4")
      (value "M04PTH")
      (footprint "eagle-import:1X04")
      (libsource (lib "eagle-import") (part "M04PTH"))
    )
    (comp (ref "L1")
      (value "INDUCTOR0805")
      (footprint "eagle-import:0805")
      (libsource (lib "eagle-import") (part "INDUCTOR0805"))
    )
    (comp (ref "L2")
      (value "INDUCTOR0805")
      (footprint "eagle-import:0805")
      (libsource (lib "eagle-import") (part "INDUCTOR0805"))
    )
    (comp (ref "L3")
      (value "INDUCTOR0805")
      (footprint "eagle-import:0805")
      (libsource (lib "eagle-import") (part "INDUCTOR0805"))
    )
    (comp (ref "L6")
      (value "INDUCTOR0805")
      (footprint "eagle-import:0805")
      (libsource (lib "eagle-import") (part "INDUCTOR0805"))
    )
    (comp (ref "PC2")
      (value "47u")
      (footprint "eagle-import:PANASONIC_D")
      (libsource (lib "eagle-import") (part "CPOL-EUD"))
    )
    (comp (ref "POT1")
      (value "SLIDER45")
      (footprint "eagle-import:SLIDER45")
      (libsource (lib "eagle-import") (part "SLIDER45"))
    )
    (comp (ref "R1")
      (value "?")
      (footprint "eagle-import:0603-RES")
      (libsource (lib "eagle-import") (part "RESISTOR0603-RES"))
    )
    (comp (ref "R2")
      (value "?")
      (footprint "eagle-import:0603-RES")
      (libsource (lib "eagle-import") (part "RESISTOR0603-RES"))
    )
    (comp (ref "R3")
      (value "270")
      (footprint "eagle-import:0603-RES")
      (libsource (lib "eagle-import") (part "RESISTOR0603-RES"))
    )
    (comp (ref "R4")
      (value "270")
      (footprint "eagle-import:0603-RES")
      (libsource (lib "eagle-import") (part "RESISTOR0603-RES"))
    )
    (comp (ref "R5")
      (value "1K5")
      (footprint "eagle-import:0603-RES")
      (libsource (lib "eagle-import") (part "RESISTOR0603-RES"))
    )
    (comp (ref "R6")
      (value "1K5")
      (footprint "eagle-import:0603-RES")
      (libsource (lib "eagle-import") (part "RESISTOR0603-RES"))
    )
    (comp (ref "R7")
      (value "270R")
      (footprint "eagle-import:0603-RES")
      (libsource (lib "eagle-import") (part "RESISTOR0603-RES"))
    )
    (comp (ref "R8")
      (value "270R")
      (footprint "eagle-import:0603-RES")
      (libsource (lib "eagle-import") (part "RESISTOR0603-RES"))
    )
    (comp (ref "R9")
      (value "10K")
      (footprint "eagle-import:0603-RES")
      (libsource (lib "eagle-import") (part "RESISTOR0603-RES"))
    )
    (comp (ref "R10")
      (value "270")
      (footprint "eagle-import:0603-RES")
      (libsource (lib "eagle-import") (part "RESISTOR0603-RES"))
    )
    (comp (ref "R11")
      (value "270")
      (footprint "eagle-import:0603-RES")
      (libsource (lib "eagle-import") (part "RESISTOR0603-RES"))
    )
    (comp (ref "R12")
      (value "270")
      (footprint "eagle-import:0603-RES")
      (libsource (lib "eagle-import") (part "RESISTOR0603-RES"))
    )
    (comp (ref "R13")
      (value "270")
      (footprint "eagle-import:0603-RES")
      (libsource (lib "eagle-import") (part "RESISTOR0603-RES"))
    )
    (comp (ref "R14")
      (value "270")
      (footprint "eagle-import:0603-RES")
      (libsource (lib "eagle-import") (part "RESISTOR0603-RES"))
    )
    (comp (ref "R15")
      (value "270")
      (footprint "eagle-import:0603-RES")
      (libsource (lib "eagle-import") (part "RESISTOR0603-RES"))
    )
    (comp (ref "R16")
      (value "270")
      (footprint "eagle-import:0603-RES")
      (libsource (lib "eagle-import") (part "RESISTOR0603-RES"))
    )
    (comp (ref "R17")
      (value "270")
      (footprint "eagle-import:0603-RES")
      (libsource (lib "eagle-import") (part "RESISTOR0603-RES"))
    )
    (comp (ref "R18")
      (value "270")
      (footprint "eagle-import:0603-RES")
      (libsource (lib "eagle-import") (part "RESISTOR0603-RES"))
    )
    (comp (ref "R19")
      (value "270")
      (footprint "eagle-import:0603-RES")
      (libsource (lib "eagle-import") (part "RESISTOR0603-RES"))
    )
    (comp (ref "R20")
      (value "270")
      (footprint "eagle-import:0603-RES")
      (libsource (lib "eagle-import") (part "RESISTOR0603-RES"))
    )
    (comp (ref "R21")
      (value "270")
      (footprint "eagle-import:0603-RES")
      (libsource (lib "eagle-import") (part "RESISTOR0603-RES"))
    )
    (comp (ref "R22")
      (value "270")
      (footprint "eagle-import:0603-RES")
      (libsource (lib "eagle-import") (part "RESISTOR0603-RES"))
    )
    (comp (ref "R23")
      (value "270")
      (footprint "eagle-import:0603-RES")
      (libsource (lib "eagle-import") (part "RESISTOR0603-RES"))
    )
    (comp (ref "R24")
      (value "270")
      (footprint "eagle-import:0603-RES")
      (libsource (lib "eagle-import") (part "RESISTOR0603-RES"))
    )
    (comp (ref "R25")
      (value "270")
      (footprint "eagle-import:0603-RES")
      (libsource (lib "eagle-import") (part "RESISTOR0603-RES"))
    )
    (comp (ref "R26")
      (value "270")
      (footprint "eagle-import:0603-RES")
      (libsource (lib "eagle-import") (part "RESISTOR0603-RES"))
    )
    (comp (ref "R27")
      (value "270")
      (footprint "eagle-import:0603-RES")
      (libsource (lib "eagle-import") (part "RESISTOR0603-RES"))
    )
    (comp (ref "R28")
      (value "270")
      (footprint "eagle-import:0603-RES")
      (libsource (lib "eagle-import") (part "RESISTOR0603-RES"))
    )
    (comp (ref "R29")
      (value "270")
      (footprint "eagle-import:0603-RES")
      (libsource (lib "eagle-import") (part "RESISTOR0603-RES"))
    )
    (comp (ref "R30")
      (value "270")
      (footprint "eagle-import:0603-RES")
      (libsource (lib "eagle-import") (part "RESISTOR0603-RES"))
    )
    (comp (ref "R31")
      (value "270")
      (footprint "eagle-import:0603-RES")
      (libsource (lib "eagle-import") (part "RESISTOR0603-RES"))
    )
    (comp (ref "R32")
      (value "270")
      (footprint "eagle-import:0603-RES")
      (libsource (lib "eagle-import") (part "RESISTOR0603-RES"))
    )
    (comp (ref "R33")
      (value "270")
      (footprint "eagle-import:0603-RES")
      (libsource (lib "eagle-import") (part "RESISTOR0603-RES"))
    )
    (comp (ref "R34")
      (value "270")
      (footprint "eagle-import:0603-RES")
      (libsource (lib "eagle-import") (part "RESISTOR0603-RES"))
    )
    (comp (ref "R35")
      (value "270")
      (footprint "eagle-import:0603-RES")
      (libsource (lib "eagle-import") (part "RESISTOR0603-RES"))
    )
    (comp (ref "R36")
      (value "270")
      (footprint "eagle-import:0603-RES")
      (libsource (lib "eagle-import") (part "RESISTOR0603-RES"))
    )
    (comp (ref "R37")
      (value "270")
      (footprint "eagle-import:0603-RES")
      (libsource (lib "eagle-import") (part "RESISTOR0603-RES"))
    )
    (comp (ref "R38")
      (value "270")
      (footprint "eagle-import:0603-RES")
      (libsource (lib "eagle-import") (part "RESISTOR0603-RES"))
    )
    (comp (ref "R39")
      (value "270")
      (footprint "eagle-import:0603-RES")
      (libsource (lib "eagle-import") (part "RESISTOR0603-RES"))
    )
    (comp (ref "R40")
      (value "270")
      (footprint "eagle-import:0603-RES")
      (libsource (lib "eagle-import") (part "RESISTOR0603-RES"))
    )
    (comp (ref "R41")
      (value "270")
      (footprint "eagle-import:0603-RES")
      (libsource (lib "eagle-import") (part "RESISTOR0603-RES"))
    )
    (comp (ref "R42")
      (value "270")
      (footprint "eagle-import:0603-RES")
      (libsource (lib "eagle-import") (part "RESISTOR0603-RES"))
    )
    (comp (ref "R43")
      (value "270")
      (footprint "eagle-import:0603-RES")
      (libsource (lib "eagle-import") (part "RESISTOR0603-RES"))
    )
    (comp (ref "R44")
      (value "270")
      (footprint "eagle-import:0603-RES")
      (libsource (lib "eagle-import") (part "RESISTOR0603-RES"))
    )
    (comp (ref "R45")
      (value "270")
      (footprint "eagle-import:0603-RES")
      (libsource (lib "eagle-import") (part "RESISTOR0603-RES"))
    )
    (comp (ref "R46")
      (value "270")
      (footprint "eagle-import:0603-RES")
      (libsource (lib "eagle-import") (part "RESISTOR0603-RES"))
    )
    (comp (ref "R47")
      (value "270")
      (footprint "eagle-import:0603-RES")
      (libsource (lib "eagle-import") (part "RESISTOR0603-RES"))
    )
    (comp (ref "R48")
      (value "270")
      (footprint "eagle-import:0603-RES")
      (libsource (lib "eagle-import") (part "RESISTOR0603-RES"))
    )
    (comp (ref "R49")
      (value "270")
      (footprint "eagle-import:0603-RES")
      (libsource (lib "eagle-import") (part "RESISTOR0603-RES"))
    )
    (comp (ref "R50")
      (value "270")
      (footprint "eagle-import:0603-RES")
      (libsource (lib "eagle-import") (part "RESISTOR0603-RES"))
    )
    (comp (ref "R51")
      (value "270")
      (footprint "eagle-import:0603-RES")
      (libsource (lib "eagle-import") (part "RESISTOR0603-RES"))
    )
    (comp (ref "R52")
      (value "270")
      (footprint "eagle-import:0603-RES")
      (libsource (lib "eagle-import") (part "RESISTOR0603-RES"))
    )
    (comp (ref "R53")
      (value "270")
      (footprint "eagle-import:0603-RES")
      (libsource (lib "eagle-import") (part "RESISTOR0603-RES"))
    )
    (comp (ref "R54")
      (value "270")
      (footprint "eagle-import:0603-RES")
      (libsource (lib "eagle-import") (part "RESISTOR0603-RES"))
    )
    (comp (ref "R55")
      (value "270")
      (footprint "eagle-import:0603-RES")
      (libsource (lib "eagle-import") (part "RESISTOR0603-RES"))
    )
    (comp (ref "R56")
      (value "0R")
      (footprint "eagle-import:0603-RES")
      (libsource (lib "eagle-import") (part "RESISTOR0603-RES"))
    )
    (comp (ref "R58")
      (value "100K")
      (footprint "eagle-import:0603-RES")
      (libsource (lib "eagle-import") (part "RESISTOR0603-RES"))
    )
    (comp (ref "R60")
      (value "270")
      (footprint "eagle-import:0603-RES")
      (libsource (lib "eagle-import") (part "RESISTOR0603-RES"))
    )
    (comp (ref "R61")
      (value "270")
      (footprint "eagle-import:0603-RES")
      (libsource (lib "eagle-import") (part "RESISTOR0603-RES"))
    )
    (comp (ref "R62")
      (value "270")
      (footprint "eagle-import:0603-RES")
      (libsource (lib "eagle-import") (part "RESISTOR0603-RES"))
    )
    (comp (ref "R63")
      (value "270")
      (footprint "eagle-import:0603-RES")
      (libsource (lib "eagle-import") (part "RESISTOR0603-RES"))
    )
    (comp (ref "R64")
      (value "270")
      (footprint "eagle-import:0603-RES")
      (libsource (lib "eagle-import") (part "RESISTOR0603-RES"))
    )
    (comp (ref "R65")
      (value "270")
      (footprint "eagle-import:0603-RES")
      (libsource (lib "eagle-import") (part "RESISTOR0603-RES"))
    )
    (comp (ref "R66")
      (value "270")
      (footprint "eagle-import:0603-RES")
      (libsource (lib "eagle-import") (part "RESISTOR0603-RES"))
    )
    (comp (ref "R67")
      (value "270")
      (footprint "eagle-import:0603-RES")
      (libsource (lib "eagle-import") (part "RESISTOR0603-RES"))
    )
    (comp (ref "R68")
      (value "270")
      (footprint "eagle-import:0603-RES")
      (libsource (lib "eagle-import") (part "RESISTOR0603-RES"))
    )
    (comp (ref "R69")
      (value "270")
      (footprint "eagle-import:0603-RES")
      (libsource (lib "eagle-import") (part "RESISTOR0603-RES"))
    )
    (comp (ref "R70")
      (value "270")
      (footprint "eagle-import:0603-RES")
      (libsource (lib "eagle-import") (part "RESISTOR0603-RES"))
    )
    (comp (ref "R71")
      (value "270")
      (footprint "eagle-import:0603-RES")
      (libsource (lib "eagle-import") (part "RESISTOR0603-RES"))
    )
    (comp (ref "RESET")
      (value "TAC_SWITCH")
      (footprint "eagle-import:PUSHBUTTON")
      (libsource (lib "eagle-import") (part "TAC_SWITCH"))
    )
    (comp (ref "RESETA")
      (value "TAC_SWITCH")
      (footprint "eagle-import:PUSHBUTTON")
      (libsource (lib "eagle-import") (part "TAC_SWITCH"))
    )
    (comp (ref "SERIAL1")
      (value "M081X08")
      (footprint "eagle-import:1X08")
      (libsource (lib "eagle-import") (part "M081X08"))
    )
    (comp (ref "SERIAL2")
      (value "M04X2")
      (footprint "eagle-import:2X4")
      (libsource (lib "eagle-import") (part "M04X2"))
    )
    (comp (ref "SERIAL3")
      (value "M081X08")
      (footprint "eagle-import:1X08")
      (libsource (lib "eagle-import") (part "M081X08"))
    )
    (comp (ref "SJ1")
      (value "SOLDERJUMPERNO")
      (footprint "eagle-import:SJ_2S-NO")
      (libsource (lib "eagle-import") (part "SOLDERJUMPERNO"))
    )
    (comp (ref "SJ2")
      (value "SOLDERJUMPERNO")
      (footprint "eagle-import:SJ_2S-NO")
      (libsource (lib "eagle-import") (part "SOLDERJUMPERNO"))
    )
    (comp (ref "SSW1")
      (value "SMART_SWITCHSMART_SWITCH_8PIN")
      (footprint "eagle-import:SMART_SWITCH")
      (libsource (lib "eagle-import") (part "SMART_SWITCHSMART_SWITCH_8PIN"))
    )
    (comp (ref "SSW2")
      (value "SMART_SWITCHSMART_SWITCH_8PIN")
      (footprint "eagle-import:SMART_SWITCH")
      (libsource (lib "eagle-import") (part "SMART_SWITCHSMART_SWITCH_8PIN"))
    )
    (comp (ref "SW1")
      (value "EC12E_SW")
      (footprint "eagle-import:ALPS_EC12E_SW")
      (fields (field (name "MPN") "EC12E2424407"))
      (libsource (lib "eagle-import") (part "EC12E_SW"))
    )
    (comp (ref "U$1")
      (value "LEDBICOLOR-AKA")
      (footprint "eagle-import:LED5MM-BICOLOR")
      (libsource (lib "eagle-import") (part "LEDBICOLOR-AKA"))
    )
    (comp (ref "U$7")
      (value "GNDPAD6MM")
      (footprint "eagle-import:3.2MMPAD6MM")
      (libsource (lib "eagle-import") (part "GNDPAD6MM"))
    )
    (comp (ref "U$15")
      (value "GNDPAD6MM")
      (footprint "eagle-import:3.2MMPAD6MM")
      (libsource (lib "eagle-import") (part "GNDPAD6MM"))
    )
    (comp (ref "U$18")
      (value "GNDPAD6MM")
      (footprint "eagle-import:3.2MMPAD6MM")
      (libsource (lib "eagle-import") (part "GNDPAD6MM"))
    )
    (comp (ref "U$20")
      (value "GNDPAD6MM")
      (footprint "eagle-import:3.2MMPAD6MM")
      (libsource (lib "eagle-import") (part "GNDPAD6MM"))
    )
    (comp (ref "U$21")
      (value "GNDPAD6MM")
      (footprint "eagle-import:3.2MMPAD6MM")
      (libsource (lib "eagle-import") (part "GNDPAD6MM"))
    )
    (comp (ref "U$34")
      (value "2BITADDR")
      (footprint "eagle-import:2BITADDR")
      (libsource (lib "eagle-import") (part "2BITADDR"))
    )
    (comp (ref "U$66")
      (value "M02X2")
      (footprint "eagle-import:2X2")
      (libsource (lib "eagle-import") (part "M02X2"))
    )
    (comp (ref "U1")
      (value "ARDUINO-MEGAFULL")
      (footprint "eagle-import:ARDUINO_MEGA")
      (libsource (lib "eagle-import") (part "ARDUINO-MEGAFULL"))
    )
    (comp (ref "UART1")
      (value "M05X2PTH")
      (footprint "eagle-import:AVR_ICSP")
      (libsource (lib "eagle-import") (part "M05X2PTH"))
    )
  )
  (nets
    (net (code "1") (name "5V") (class "Default")
      (node (ref "B1") (pin "COM") (pinfunction "A_COM") (pintype "bidirectional"))
      (node (ref "B10") (pin "COM") (pinfunction "A_COM") (pintype "bidirectional"))
      (node (ref "B10ALT") (pin "COM") (pinfunction "A_COM") (pintype "bidirectional"))
      (node (ref "B11") (pin "COM") (pinfunction "A_COM") (pintype "bidirectional"))
      (node (ref "B11ALT") (pin "COM") (pinfunction "A_COM") (pintype "bidirectional"))
      (node (ref "B12") (pin "COM") (pinfunction "A_COM") (pintype "bidirectional"))
      (node (ref "B12ALT") (pin "COM") (pinfunction "A_COM") (pintype "bidirectional"))
      (node (ref "B13") (pin "COM") (pinfunction "A_COM") (pintype "bidirectional"))
      (node (ref "B14") (pin "COM") (pinfunction "A_COM") (pintype "bidirectional"))
      (node (ref "B14ALT") (pin "COM") (pinfunction "A_COM") (pintype "bidirectional"))
      (node (ref "B15") (pin "COM") (pinfunction "A_COM") (pintype "bidirectional"))
      (node (ref "B16") (pin "COM") (pinfunction "A_COM") (pintype "bidirectional"))
      (node (ref "B17") (pin "COM") (pinfunction "A_COM") (pintype "bidirectional"))
      (node (ref "B17ALT") (pin "COM") (pinfunction "A_COM") (pintype "bidirectional"))
      (node (ref "B18") (pin "COM") (pinfunction "A_COM") (pintype "bidirectional"))
      (node (ref "B19") (pin "COM") (pinfunction "A_COM") (pintype "bidirectional"))
      (node (ref "B1ALT") (pin "COM") (pinfunction "A_COM") (pintype "bidirectional"))
      (node (ref "B2") (pin "COM") (pinfunction "A_COM") (pintype "bidirectional"))
      (node (ref "B20") (pin "COM") (pinfunction "A_COM") (pintype "bidirectional"))
      (node (ref "B20ALT") (pin "COM") (pinfunction "A_COM") (pintype "bidirectional"))
      (node (ref "B21") (pin "COM") (pinfunction "A_COM") (pintype "bidirectional"))
      (node (ref "B21ALT") (pin "COM") (pinfunction "A_COM") (pintype "bidirectional"))
      (node (ref "B22") (pin "COM") (pinfunction "A_COM") (pintype "bidirectional"))
      (node (ref "B23") (pin "COM") (pinfunction "A_COM") (pintype "bidirectional"))
      (node (ref "B24") (pin "COM") (pinfunction "A_COM") (pintype "bidirectional"))
      (node (ref "B25") (pin "COM") (pinfunction "A_COM") (pintype "bidirectional"))
      (node (ref "B26") (pin "COM") (pinfunction "A_COM") (pintype "bidirectional"))
      (node (ref "B26ALT") (pin "COM") (pinfunction "A_COM") (pintype "bidirectional"))
      (node (ref "B27") (pin "COM") (pinfunction "A_COM") (pintype "bidirectional"))
      (node (ref "B27ALT") (pin "COM") (pinfunction "A_COM") (pintype "bidirectional"))
      (node (ref "B28") (pin "COM") (pinfunction "A_COM") (pintype "bidirectional"))
      (node (ref "B29") (pin "COM") (pinfunction "A_COM") (pintype "bidirectional"))
      (node (ref "B2ALT") (pin "COM") (pinfunction "A_COM") (pintype "bidirectional"))
      (node (ref "B3") (pin "COM") (pinfunction "A_COM") (pintype "bidirectional"))
      (node (ref "B30") (pin "COM") (pinfunction "A_COM") (pintype "bidirectional"))
      (node (ref "B3ALT") (pin "COM") (pinfunction "A_COM") (pintype "bidirectional"))
      (node (ref "B4") (pin "COM") (pinfunction "A_COM") (pintype "bidirectional"))
      (node (ref "B4ALT") (pin "COM") (pinfunction "A_COM") (pintype "bidirectional"))
      (node (ref "B5") (pin "COM") (pinfunction "A_COM") (pintype "bidirectional"))
      (node (ref "B5ALT") (pin "COM") (pinfunction "A_COM") (pintype "bidirectional"))
      (node (ref "B6") (pin "COM") (pinfunction "A_COM") (pintype "bidirectional"))
      (node (ref "B6ALT") (pin "COM") (pinfunction "A_COM") (pintype "bidirectional"))
      (node (ref "B7") (pin "COM") (pinfunction "A_COM") (pintype "bidirectional"))
      (node (ref "B7ALT") (pin "COM") (pinfunction "A_COM") (pintype "bidirectional"))
      (node (ref "B8") (pin "COM") (pinfunction "A_COM") (pintype "bidirectional"))
      (node (ref "B8ALT") (pin "COM") (pinfunction "A_COM") (pintype "bidirectional"))
      (node (ref "B9") (pin "COM") (pinfunction "A_COM") (pintype "bidirectional"))
      (node (ref "B9ALT") (pin "COM") (pinfunction "A_COM") (pintype "bidirectional"))
      (node (ref "C10") (pin "1") (pinfunction "1_1") (pintype "passive"))
      (node (ref "C11") (pin "1") (pinfunction "1_1") (pintype "passive"))
      (node (ref "C12") (pin "1") (pinfunction "1_1") (pintype "passive"))
      (node (ref "C13") (pin "1") (pinfunction "1_1") (pintype "passive"))
      (node (ref "C14") (pin "1") (pinfunction "1_1") (pintype "passive"))
      (node (ref "C15") (pin "2") (pinfunction "2_2") (pintype "passive"))
      (node (ref "C16") (pin "1") (pinfunction "1_1") (pintype "passive"))
      (node (ref "C17") (pin "1") (pinfunction "1_1") (pintype "passive"))
      (node (ref "C18") (pin "1") (pinfunction "1_1") (pintype "passive"))
      (node (ref "C19") (pin "1") (pinfunction "1_1") (pintype "passive"))
      (node (ref "C20") (pin "1") (pinfunction "1_1") (pintype "passive"))
      (node (ref "C21") (pin "2") (pinfunction "2_2") (pintype "passive"))
      (node (ref "C22") (pin "1") (pinfunction "1_1") (pintype "passive"))
      (node (ref "C23") (pin "1") (pinfunction "1_1") (pintype "passive"))
      (node (ref "C27") (pin "1") (pinfunction "1_1") (pintype "passive"))
      (node (ref "C30") (pin "2") (pinfunction "2_2") (pintype "passive"))
      (node (ref "C4") (pin "2") (pinfunction "2_2") (pintype "passive"))
      (node (ref "C5") (pin "1") (pinfunction "1_1") (pintype "passive"))
      (node (ref "C7") (pin "1") (pinfunction "1_1") (pintype "passive"))
      (node (ref "C8") (pin "1") (pinfunction "1_1") (pintype "passive"))
      (node (ref "C9") (pin "1") (pinfunction "1_1") (pintype "passive"))
      (node (ref "IC1") (pin "18") (pinfunction "~{RESET}_18") (pintype "input"))
      (node (ref "IC1") (pin "9") (pinfunction "VDD_9") (pintype "power_in"))
      (node (ref "IC2") (pin "24") (pinfunction "A5_24") (pintype "input"))
      (node (ref "IC2") (pin "28") (pinfunction "VDD_28") (pintype "power_in"))
      (node (ref "IC2") (pin "4") (pinfunction "A3_4") (pintype "input"))
      (node (ref "IC2") (pin "5") (pinfunction "A4_5") (pintype "input"))
      (node (ref "IC3") (pin "24") (pinfunction "A5_24") (pintype "input"))
      (node (ref "IC3") (pin "28") (pinfunction "VDD_28") (pintype "power_in"))
      (node (ref "IC4") (pin "1") (pinfunction "A0_1") (pintype "input"))
      (node (ref "IC4") (pin "24") (pinfunction "A5_24") (pintype "input"))
      (node (ref "IC4") (pin "28") (pinfunction "VDD_28") (pintype "power_in"))
      (node (ref "IC4") (pin "4") (pinfunction "A3_4") (pintype "input"))
      (node (ref "IC4") (pin "5") (pinfunction "A4_5") (pintype "input"))
      (node (ref "IC5") (pin "1") (pinfunction "A0_1") (pintype "input"))
      (node (ref "IC5") (pin "24") (pinfunction "A5_24") (pintype "input"))
      (node (ref "IC5") (pin "28") (pinfunction "VDD_28") (pintype "power_in"))
      (node (ref "IC6") (pin "15") (pinfunction "A0_15") (pintype "input"))
      (node (ref "IC6") (pin "18") (pinfunction "~{RESET}_18") (pintype "input"))
      (node (ref "IC6") (pin "9") (pinfunction "VDD_9") (pintype "power_in"))
      (node (ref "IC7") (pin "16") (pinfunction "A1_16") (pintype "input"))
      (node (ref "IC7") (pin "18") (pinfunction "~{RESET}_18") (pintype "input"))
      (node (ref "IC7") (pin "9") (pinfunction "VDD_9") (pintype "power_in"))
      (node (ref "IC8") (pin "15") (pinfunction "A0_15") (pintype "input"))
      (node (ref "IC8") (pin "16") (pinfunction "A1_16") (pintype "input"))
      (node (ref "IC8") (pin "18") (pinfunction "~{RESET}_18") (pintype "input"))
      (node (ref "IC8") (pin "9") (pinfunction "VDD_9") (pintype "power_in"))
      (node (ref "IC9") (pin "14") (pinfunction "VCC_14") (pintype "power_in"))
      (node (ref "JP3") (pin "2") (pinfunction "2_2") (pintype "passive"))
      (node (ref "JP3") (pin "3") (pinfunction "3_3") (pintype "passive"))
      (node (ref "JP4") (pin "3") (pinfunction "3_3") (pintype "passive"))
      (node (ref "L3") (pin "1") (pinfunction "1_1") (pintype "passive"))
      (node (ref "PC2") (pin "+") (pinfunction "+_+") (pintype "passive"))
      (node (ref "POT1") (pin "1") (pinfunction "E_1") (pintype "passive"))
      (node (ref "R58") (pin "2") (pinfunction "2_2") (pintype "passive"))
      (node (ref "R9") (pin "1") (pinfunction "1_1") (pintype "passive"))
      (node (ref "SERIAL1") (pin "2") (pinfunction "2_2") (pintype "passive"))
      (node (ref "SERIAL3") (pin "2") (pinfunction "2_2") (pintype "passive"))
      (node (ref "SSW1") (pin "4") (pinfunction "VDD_4") (pintype "bidirectional"))
      (node (ref "SSW2") (pin "4") (pinfunction "VDD_4") (pintype "bidirectional"))
      (node (ref "U$34") (pin "H2") (pinfunction "VCC_H2") (pintype "passive"))
      (node (ref "U$34") (pin "H3") (pinfunction "VCC_H3") (pintype "passive"))
    )
    (net (code "2") (name "5V_RAW") (class "Default")
      (node (ref "C3") (pin "1") (pinfunction "1_1") (pintype "passive"))
      (node (ref "C6") (pin "1") (pinfunction "1_1") (pintype "passive"))
      (node (ref "L1") (pin "1") (pinfunction "1_1") (pintype "passive"))
      (node (ref "L2") (pin "2") (pinfunction "2_2") (pintype "passive"))
      (node (ref "L3") (pin "2") (pinfunction "2_2") (pintype "passive"))
      (node (ref "L6") (pin "1") (pinfunction "1_1") (pintype "passive"))
      (node (ref "R5") (pin "2") (pinfunction "2_2") (pintype "passive"))
      (node (ref "R6") (pin "2") (pinfunction "2_2") (pintype "passive"))
      (node (ref "U1") (pin "5V@0") (pinfunction "5V_5V@0") (pintype "bidirectional"))
      (node (ref "U1") (pin "5V@1") (pinfunction "5V_5V@1") (pintype "bidirectional"))
      (node (ref "U1") (pin "5V@2") (pinfunction "5V_5V@2") (pintype "bidirectional"))
    )
    (net (code "3") (name "A0") (class "Default")
      (node (ref "JP4") (pin "2") (pinfunction "2_2") (pintype "passive"))
      (node (ref "POT1") (pin "2A") (pinfunction "S_2A") (pintype "passive"))
      (node (ref "SERIAL1") (pin "5") (pinfunction "5_5") (pintype "passive"))
      (node (ref "SERIAL2") (pin "5") (pinfunction "5_5") (pintype "passive"))
      (node (ref "SERIAL3") (pin "5") (pinfunction "5_5") (pintype "passive"))
      (node (ref "U1") (pin "A0") (pinfunction "A0(RX0)_A0") (pintype "bidirectional"))
    )
    (net (code "4") (name "A1") (class "Default")
      (node (ref "CONF-A1") (pin "2") (pinfunction "2_2") (pintype "passive"))
      (node (ref "U1") (pin "A1") (pinfunction "A1(TX0)_A1") (pintype "bidirectional"))
    )
    (net (code "5") (name "A2") (class "Default")
      (node (ref "IC1") (pin "17") (pinfunction "A2_17") (pintype "input"))
      (node (ref "IC2") (pin "3") (pinfunction "A2_3") (pintype "input"))
      (node (ref "IC3") (pin "3") (pinfunction "A2_3") (pintype "input"))
      (node (ref "IC4") (pin "3") (pinfunction "A2_3") (pintype "input"))
      (node (ref "IC5") (pin "3") (pinfunction "A2_3") (pintype "input"))
      (node (ref "IC6") (pin "17") (pinfunction "A2_17") (pintype "input"))
      (node (ref "IC7") (pin "17") (pinfunction "A2_17") (pintype "input"))
      (node (ref "IC8") (pin "17") (pinfunction "A2_17") (pintype "input"))
      (node (ref "U$34") (pin "A2") (pinfunction "A2_A2") (pintype "passive"))
    )
    (net (code "6") (name "A3") (class "Default")
      (node (ref "ANLGDAISY-MAIN") (pin "2") (pinfunction "2_2") (pintype "passive"))
      (node (ref "U1") (pin "A3") (pinfunction "A3_A3") (pintype "bidirectional"))
    )
    (net (code "7") (name "A4") (class "Default")
      (node (ref "ANLGDAISY-MAIN") (pin "3") (pinfunction "3_3") (pintype "passive"))
      (node (ref "U1") (pin "A4") (pinfunction "A4_A4") (pintype "bidirectional"))
    )
    (net (code "8") (name "A5") (class "Default")
      (node (ref "ANLGDAISY-MAIN") (pin "4") (pinfunction "4_4") (pintype "passive"))
      (node (ref "U1") (pin "A5") (pinfunction "A5_A5") (pintype "bidirectional"))
    )
    (net (code "9") (name "A6") (class "Default")
      (node (ref "U1") (pin "A6") (pinfunction "A6_A6") (pintype "bidirectional"))
    )
    (net (code "10") (name "A7") (class "Default")
      (node (ref "U1") (pin "A7") (pinfunction "A7_A7") (pintype "bidirectional"))
    )
    (net (code "11") (name "A8") (class "Default")
      (node (ref "U1") (pin "A8") (pinfunction "A8_A8") (pintype "bidirectional"))
    )
    (net (code "12") (name "A9") (class "Default")
      (node (ref "U1") (pin "A9") (pinfunction "A9_A9") (pintype "bidirectional"))
    )
    (net (code "13") (name "A10") (class "Default")
      (node (ref "U1") (pin "A10") (pinfunction "A10_A10") (pintype "bidirectional"))
    )
    (net (code "14") (name "A11") (class "Default")
      (node (ref "U1") (pin "A11") (pinfunction "A11_A11") (pintype "bidirectional"))
    )
    (net (code "15") (name "A12") (class "Default")
      (node (ref "ANLGDAISY-MAIN") (pin "7") (pinfunction "7_7") (pintype "passive"))
      (node (ref "JOYSTICKS") (pin "2") (pinfunction "2_2") (pintype "passive"))
      (node (ref "U1") (pin "A12") (pinfunction "A12_A12") (pintype "bidirectional"))
    )
    (net (code "16") (name "A13") (class "Default")
      (node (ref "ANLGDAISY-MAIN") (pin "8") (pinfunction "8_8") (pintype "passive"))
      (node (ref "JOYSTICKS") (pin "3") (pinfunction "3_3") (pintype "passive"))
      (node (ref "U1") (pin "A13") (pinfunction "A13_A13") (pintype "bidirectional"))
    )
    (net (code "17") (name "A14") (class "Default")
      (node (ref "ANLGDAISY-MAIN") (pin "5") (pinfunction "5_5") (pintype "passive"))
      (node (ref "JOYSTICKS") (pin "5") (pinfunction "5_5") (pintype "passive"))
      (node (ref "U1") (pin "A14") (pinfunction "A14_A14") (pintype "bidirectional"))
    )
    (net (code "18") (name "A15") (class "Default")
      (node (ref "ANLGDAISY-MAIN") (pin "6") (pinfunction "6_6") (pintype "passive"))
      (node (ref "JOYSTICKS") (pin "6") (pinfunction "6_6") (pintype "passive"))
      (node (ref "U1") (pin "A15") (pinfunction "A15_A15") (pintype "bidirectional"))
    )
    (net (code "19") (name "AD0") (class "Default")
      (node (ref "C26") (pin "1") (pinfunction "1_1") (pintype "passive"))
      (node (ref "IC8") (pin "1") (pinfunction "GPB0_1") (pintype "bidirectional"))
      (node (ref "SW1") (pin "E") (pinfunction "2_E") (pintype "passive"))
      (node (ref "U$66") (pin "4") (pinfunction "4_4") (pintype "passive"))
    )
    (net (code "20") (name "AN2") (class "Default")
      (node (ref "ANLGDAISY-MAIN") (pin "1") (pinfunction "1_1") (pintype "passive"))
      (node (ref "U1") (pin "A2") (pinfunction "A2_A2") (pintype "bidirectional"))
    )
    (net (code "21") (name "D2") (class "Default")
      (node (ref "IC8") (pin "21") (pinfunction "GPA0_21") (pintype "bidirectional"))
      (node (ref "IC9") (pin "12") (pinfunction "O_12") (pintype "output"))
    )
    (net (code "22") (name "D3") (class "Default")
      (node (ref "C25") (pin "1") (pinfunction "1_1") (pintype "passive"))
      (node (ref "IC8") (pin "22") (pinfunction "GPA1_22") (pintype "bidirectional"))
      (node (ref "SW1") (pin "A") (pinfunction "A_A") (pintype "passive"))
      (node (ref "U$66") (pin "3") (pinfunction "3_3") (pintype "passive"))
    )
    (net (code "23") (name "D6") (class "Default")
      (node (ref "U1") (pin "6") (pinfunction "6_6") (pintype "bidirectional"))
    )
    (net (code "24") (name "D7") (class "Default")
      (node (ref "U1") (pin "7") (pinfunction "7_7") (pintype "bidirectional"))
    )
    (net (code "25") (name "D8") (class "Default")
      (node (ref "U1") (pin "8") (pinfunction "8_8") (pintype "bidirectional"))
    )
    (net (code "26") (name "D9") (class "Default")
      (node (ref "U1") (pin "9") (pinfunction "9_9") (pintype "bidirectional"))
    )
    (net (code "27") (name "D22") (class "Default")
      (node (ref "R7") (pin "2") (pinfunction "2_2") (pintype "passive"))
      (node (ref "U1") (pin "22") (pinfunction "22_22") (pintype "bidirectional"))
    )
    (net (code "28") (name "D23") (class "Default")
      (node (ref "R8") (pin "2") (pinfunction "2_2") (pintype "passive"))
      (node (ref "U1") (pin "23") (pinfunction "23_23") (pintype "bidirectional"))
    )
    (net (code "29") (name "D24") (class "Default")
      (node (ref "U1") (pin "24") (pinfunction "24_24") (pintype "bidirectional"))
    )
    (net (code "30") (name "D37") (class "Default")
      (node (ref "CONF") (pin "3") (pinfunction "3_3") (pintype "passive"))
      (node (ref "CONF-A1") (pin "1") (pinfunction "1_1") (pintype "passive"))
      (node (ref "R9") (pin "2") (pinfunction "2_2") (pintype "passive"))
      (node (ref "U1") (pin "37") (pinfunction "37_37") (pintype "bidirectional"))
    )
    (net (code "31") (name "EXT1") (class "Default")
      (node (ref "U1") (pin "25") (pinfunction "25_25") (pintype "bidirectional"))
    )
    (net (code "32") (name "EXT2") (class "Default")
      (node (ref "U1") (pin "26") (pinfunction "26_26") (pintype "bidirectional"))
    )
    (net (code "33") (name "EXT3") (class "Default")
      (node (ref "U1") (pin "27") (pinfunction "27_27") (pintype "bidirectional"))
    )
    (net (code "34") (name "EXT4") (class "Default")
      (node (ref "U1") (pin "28") (pinfunction "28_28") (pintype "bidirectional"))
    )
    (net (code "35") (name "EXT5") (class "Default")
      (node (ref "U1") (pin "29") (pinfunction "29_29") (pintype "bidirectional"))
    )
    (net (code "36") (name "EXT6") (class "Default")
      (node (ref "U1") (pin "30") (pinfunction "30_30") (pintype "bidirectional"))
    )
    (net (code "37") (name "EXT7") (class "Default")
      (node (ref "U1") (pin "31") (pinfunction "31_31") (pintype "bidirectional"))
    )
    (net (code "38") (name "EXT8") (class "Default")
      (node (ref "U1") (pin "32") (pinfunction "32_32") (pintype "bidirectional"))
    )
    (net (code "39") (name "GND") (class "Default")
      (node (ref "B1") (pin "P$4") (pinfunction "SW1_P$4") (pintype "bidirectional"))
      (node (ref "B10") (pin "P$4") (pinfunction "SW1_P$4") (pintype "bidirectional"))
      (node (ref "B10ALT") (pin "P$4") (pinfunction "SW1_P$4") (pintype "bidirectional"))
      (node (ref "B11") (pin "P$4") (pinfunction "SW1_P$4") (pintype "bidirectional"))
      (node (ref "B11ALT") (pin "P$4") (pinfunction "SW1_P$4") (pintype "bidirectional"))
      (node (ref "B12") (pin "P$4") (pinfunction "SW1_P$4") (pintype "bidirectional"))
      (node (ref "B12ALT") (pin "P$4") (pinfunction "SW1_P$4") (pintype "bidirectional"))
      (node (ref "B13") (pin "P$4") (pinfunction "SW1_P$4") (pintype "bidirectional"))
      (node (ref "B14") (pin "P$4") (pinfunction "SW1_P$4") (pintype "bidirectional"))
      (node (ref "B14ALT") (pin "P$4") (pinfunction "SW1_P$4") (pintype "bidirectional"))
      (node (ref "B15") (pin "P$4") (pinfunction "SW1_P$4") (pintype "bidirectional"))
      (node (ref "B16") (pin "P$4") (pinfunction "SW1_P$4") (pintype "bidirectional"))
      (node (ref "B17") (pin "P$4") (pinfunction "SW1_P$4") (pintype "bidirectional"))
      (node (ref "B17ALT") (pin "P$4") (pinfunction "SW1_P$4") (pintype "bidirectional"))
      (node (ref "B18") (pin "P$4") (pinfunction "SW1_P$4") (pintype "bidirectional"))
      (node (ref "B19") (pin "P$4") (pinfunction "SW1_P$4") (pintype "bidirectional"))
      (node (ref "B1ALT") (pin "P$4") (pinfunction "SW1_P$4") (pintype "bidirectional"))
      (node (ref "B2") (pin "P$4") (pinfunction "SW1_P$4") (pintype "bidirectional"))
      (node (ref "B20") (pin "P$4") (pinfunction "SW1_P$4") (pintype "bidirectional"))
      (node (ref "B20ALT") (pin "P$4") (pinfunction "SW1_P$4") (pintype "bidirectional"))
      (node (ref "B21") (pin "P$4") (pinfunction "SW1_P$4") (pintype "bidirectional"))
      (node (ref "B21ALT") (pin "P$4") (pinfunction "SW1_P$4") (pintype "bidirectional"))
      (node (ref "B22") (pin "P$4") (pinfunction "SW1_P$4") (pintype "bidirectional"))
      (node (ref "B23") (pin "P$4") (pinfunction "SW1_P$4") (pintype "bidirectional"))
      (node (ref "B24") (pin "P$4") (pinfunction "SW1_P$4") (pintype "bidirectional"))
      (node (ref "B25") (pin "P$4") (pinfunction "SW1_P$4") (pintype "bidirectional"))
      (node (ref "B26") (pin "P$4") (pinfunction "SW1_P$4") (pintype "bidirectional"))
      (node (ref "B26ALT") (pin "P$4") (pinfunction "SW1_P$4") (pintype "bidirectional"))
      (node (ref "B27") (pin "P$4") (pinfunction "SW1_P$4") (pintype "bidirectional"))
      (node (ref "B27ALT") (pin "P$4") (pinfunction "SW1_P$4") (pintype "bidirectional"))
      (node (ref "B28") (pin "P$4") (pinfunction "SW1_P$4") (pintype "bidirectional"))
      (node (ref "B29") (pin "P$4") (pinfunction "SW1_P$4") (pintype "bidirectional"))
      (node (ref "B2ALT") (pin "P$4") (pinfunction "SW1_P$4") (pintype "bidirectional"))
      (node (ref "B3") (pin "P$4") (pinfunction "SW1_P$4") (pintype "bidirectional"))
      (node (ref "B30") (pin "P$4") (pinfunction "SW1_P$4") (pintype "bidirectional"))
      (node (ref "B3ALT") (pin "P$4") (pinfunction "SW1_P$4") (pintype "bidirectional"))
      (node (ref "B4") (pin "P$4") (pinfunction "SW1_P$4") (pintype "bidirectional"))
      (node (ref "B4ALT") (pin "P$4") (pinfunction "SW1_P$4") (pintype "bidirectional"))
      (node (ref "B5") (pin "P$4") (pinfunction "SW1_P$4") (pintype "bidirectional"))
      (node (ref "B5ALT") (pin "P$4") (pinfunction "SW1_P$4") (pintype "bidirectional"))
      (node (ref "B6") (pin "P$4") (pinfunction "SW1_P$4") (pintype "bidirectional"))
      (node (ref "B6ALT") (pin "P$4") (pinfunction "SW1_P$4") (pintype "bidirectional"))
      (node (ref "B7") (pin "P$4") (pinfunction "SW1_P$4") (pintype "bidirectional"))
      (node (ref "B7ALT") (pin "P$4") (pinfunction "SW1_P$4") (pintype "bidirectional"))
      (node (ref "B8") (pin "P$4") (pinfunction "SW1_P$4") (pintype "bidirectional"))
      (node (ref "B8ALT") (pin "P$4") (pinfunction "SW1_P$4") (pintype "bidirectional"))
      (node (ref "B9") (pin "P$4") (pinfunction "SW1_P$4") (pintype "bidirectional"))
      (node (ref "B9ALT") (pin "P$4") (pinfunction "SW1_P$4") (pintype "bidirectional"))
      (node (ref "C1") (pin "2") (pinfunction "2_2") (pintype "passive"))
      (node (ref "C10") (pin "2") (pinfunction "2_2") (pintype "passive"))
      (node (ref "C11") (pin "2") (pinfunction "2_2") (pintype "passive"))
      (node (ref "C12") (pin "2") (pinfunction "2_2") (pintype "passive"))
      (node (ref "C13") (pin "2") (pinfunction "2_2") (pintype "passive"))
      (node (ref "C14") (pin "2") (pinfunction "2_2") (pintype "passive"))
      (node (ref "C15") (pin "1") (pinfunction "1_1") (pintype "passive"))
      (node (ref "C16") (pin "2") (pinfunction "2_2") (pintype "passive"))
      (node (ref "C17") (pin "2") (pinfunction "2_2") (pintype "passive"))
      (node (ref "C18") (pin "2") (pinfunction "2_2") (pintype "passive"))
      (node (ref "C19") (pin "2") (pinfunction "2_2") (pintype "passive"))
      (node (ref "C2") (pin "2") (pinfunction "2_2") (pintype "passive"))
      (node (ref "C20") (pin "2") (pinfunction "2_2") (pintype "passive"))
      (node (ref "C21") (pin "1") (pinfunction "1_1") (pintype "passive"))
      (node (ref "C22") (pin "2") (pinfunction "2_2") (pintype "passive"))
      (node (ref "C23") (pin "2") (pinfunction "2_2") (pintype "passive"))
      (node (ref "C24") (pin "2") (pinfunction "2_2") (pintype "passive"))
      (node (ref "C25") (pin "2") (pinfunction "2_2") (pintype "passive"))
      (node (ref "C26") (pin "2") (pinfunction "2_2") (pintype "passive"))
      (node (ref "C27") (pin "2") (pinfunction "2_2") (pintype "passive"))
      (node (ref "C3") (pin "2") (pinfunction "2_2") (pintype "passive"))
      (node (ref "C30") (pin "1") (pinfunction "1_1") (pintype "passive"))
      (node (ref "C4") (pin "1") (pinfunction "1_1") (pintype "passive"))
      (node (ref "C5") (pin "2") (pinfunction "2_2") (pintype "passive"))
      (node (ref "C6") (pin "2") (pinfunction "2_2") (pintype "passive"))
      (node (ref "C7") (pin "2") (pinfunction "2_2") (pintype "passive"))
      (node (ref "C8") (pin "2") (pinfunction "2_2") (pintype "passive"))
      (node (ref "C9") (pin "2") (pinfunction "2_2") (pintype "passive"))
      (node (ref "CONF") (pin "1") (pinfunction "1_1") (pintype "passive"))
      (node (ref "IC1") (pin "10") (pinfunction "VSS_10") (pintype "power_in"))
      (node (ref "IC1") (pin "15") (pinfunction "A0_15") (pintype "input"))
      (node (ref "IC1") (pin "16") (pinfunction "A1_16") (pintype "input"))
      (node (ref "IC2") (pin "1") (pinfunction "A0_1") (pintype "input"))
      (node (ref "IC2") (pin "14") (pinfunction "GND_14") (pintype "power_in"))
      (node (ref "IC2") (pin "2") (pinfunction "A1_2") (pintype "input"))
      (node (ref "IC2") (pin "23") (pinfunction "OE_23") (pintype "input"))
      (node (ref "IC2") (pin "25") (pinfunction "EXTCLK_25") (pintype "input"))
      (node (ref "IC3") (pin "1") (pinfunction "A0_1") (pintype "input"))
      (node (ref "IC3") (pin "14") (pinfunction "GND_14") (pintype "power_in"))
      (node (ref "IC3") (pin "2") (pinfunction "A1_2") (pintype "input"))
      (node (ref "IC3") (pin "23") (pinfunction "OE_23") (pintype "input"))
      (node (ref "IC3") (pin "25") (pinfunction "EXTCLK_25") (pintype "input"))
      (node (ref "IC3") (pin "4") (pinfunction "A3_4") (pintype "input"))
      (node (ref "IC3") (pin "5") (pinfunction "A4_5") (pintype "input"))
      (node (ref "IC4") (pin "14") (pinfunction "GND_14") (pintype "power_in"))
      (node (ref "IC4") (pin "2") (pinfunction "A1_2") (pintype "input"))
      (node (ref "IC4") (pin "23") (pinfunction "OE_23") (pintype "input"))
      (node (ref "IC4") (pin "25") (pinfunction "EXTCLK_25") (pintype "input"))
      (node (ref "IC5") (pin "14") (pinfunction "GND_14") (pintype "power_in"))
      (node (ref "IC5") (pin "2") (pinfunction "A1_2") (pintype "input"))
      (node (ref "IC5") (pin "23") (pinfunction "OE_23") (pintype "input"))
      (node (ref "IC5") (pin "25") (pinfunction "EXTCLK_25") (pintype "input"))
      (node (ref "IC5") (pin "4") (pinfunction "A3_4") (pintype "input"))
      (node (ref "IC5") (pin "5") (pinfunction "A4_5") (pintype "input"))
      (node (ref "IC6") (pin "10") (pinfunction "VSS_10") (pintype "power_in"))
      (node (ref "IC6") (pin "16") (pinfunction "A1_16") (pintype "input"))
      (node (ref "IC7") (pin "10") (pinfunction "VSS_10") (pintype "power_in"))
      (node (ref "IC7") (pin "15") (pinfunction "A0_15") (pintype "input"))
      (node (ref "IC8") (pin "10") (pinfunction "VSS_10") (pintype "power_in"))
      (node (ref "IC9") (pin "1") (pinfunction "I_1") (pintype "input"))
      (node (ref "IC9") (pin "11") (pinfunction "I_11") (pintype "input"))
      (node (ref "IC9") (pin "3") (pinfunction "I_3") (pintype "input"))
      (node (ref "IC9") (pin "5") (pinfunction "I_5") (pintype "input"))
      (node (ref "IC9") (pin "7") (pinfunction "GND_7") (pintype "power_in"))
      (node (ref "IC9") (pin "9") (pinfunction "I_9") (pintype "input"))
      (node (ref "JOYSTICKS") (pin "8") (pinfunction "8_8") (pintype "passive"))
      (node (ref "JP3") (pin "1") (pinfunction "1_1") (pintype "passive"))
      (node (ref "JP3") (pin "4") (pinfunction "4_4") (pintype "passive"))
      (node (ref "JP4") (pin "1") (pinfunction "1_1") (pintype "passive"))
      (node (ref "JP4") (pin "4") (pinfunction "4_4") (pintype "passive"))
      (node (ref "PC2") (pin "-") (pinfunction "-_-") (pintype "passive"))
      (node (ref "POT1") (pin "3") (pinfunction "A_3") (pintype "passive"))
      (node (ref "RESET") (pin "1") (pinfunction "1_1") (pintype "passive"))
      (node (ref "RESETA") (pin "1") (pinfunction "1_1") (pintype "passive"))
      (node (ref "SERIAL1") (pin "1") (pinfunction "1_1") (pintype "passive"))
      (node (ref "SERIAL2") (pin "1") (pinfunction "1_1") (pintype "passive"))
      (node (ref "SERIAL3") (pin "1") (pinfunction "1_1") (pintype "passive"))
      (node (ref "SSW1") (pin "1") (pinfunction "SW1_1") (pintype "bidirectional"))
      (node (ref "SSW1") (pin "3") (pinfunction "GND_3") (pintype "bidirectional"))
      (node (ref "SSW2") (pin "1") (pinfunction "SW1_1") (pintype "bidirectional"))
      (node (ref "SSW2") (pin "3") (pinfunction "GND_3") (pintype "bidirectional"))
      (node (ref "SW1") (pin "C") (pinfunction "C_C") (pintype "passive"))
      (node (ref "SW1") (pin "D") (pinfunction "1_D") (pintype "passive"))
      (node (ref "U$1") (pin "K1") (pinfunction "P$1_K1") (pintype "bidirectional"))
      (node (ref "U$15") (pin "P$1") (pinfunction "1_P$1") (pintype "passive"))
      (node (ref "U$18") (pin "P$1") (pinfunction "1_P$1") (pintype "passive"))
      (node (ref "U$20") (pin "P$1") (pinfunction "1_P$1") (pintype "passive"))
      (node (ref "U$21") (pin "P$1") (pinfunction "1_P$1") (pintype "passive"))
      (node (ref "U$34") (pin "L2") (pinfunction "GND_L2") (pintype "passive"))
      (node (ref "U$34") (pin "L3") (pinfunction "GND_L3") (pintype "passive"))
      (node (ref "U$66") (pin "1") (pinfunction "1_1") (pintype "passive"))
      (node (ref "U$7") (pin "P$1") (pinfunction "1_P$1") (pintype "passive"))
      (node (ref "U1") (pin "GND@0") (pinfunction "GND_GND@0") (pintype "bidirectional"))
      (node (ref "U1") (pin "GND@1") (pinfunction "GND_GND@1") (pintype "bidirectional"))
      (node (ref "U1") (pin "GND@2") (pinfunction "GND_GND@2") (pintype "bidirectional"))
      (node (ref "U1") (pin "GND@3") (pinfunction "GND_GND@3") (pintype "bidirectional"))
      (node (ref "U1") (pin "GND@4") (pinfunction "GND_GND@4") (pintype "bidirectional"))
      (node (ref "UART1") (pin "5") (pinfunction "5_5") (pintype "passive"))
    )
    (net (code "40") (name "GPA0") (class "Default")
      (node (ref "B8") (pin "P$5") (pinfunction "SW2_P$5") (pintype "bidirectional"))
      (node (ref "B8ALT") (pin "P$5") (pinfunction "SW2_P$5") (pintype "bidirectional"))
      (node (ref "IC1") (pin "21") (pinfunction "GPA0_21") (pintype "bidirectional"))
    )
    (net (code "41") (name "GPA0_2") (class "Default")
      (node (ref "IC7") (pin "21") (pinfunction "GPA0_21") (pintype "bidirectional"))
      (node (ref "SSW1") (pin "2") (pinfunction "SW2_2") (pintype "bidirectional"))
    )
    (net (code "42") (name "GPA1") (class "Default")
      (node (ref "B7") (pin "P$5") (pinfunction "SW2_P$5") (pintype "bidirectional"))
      (node (ref "B7ALT") (pin "P$5") (pinfunction "SW2_P$5") (pintype "bidirectional"))
      (node (ref "IC1") (pin "22") (pinfunction "GPA1_22") (pintype "bidirectional"))
    )
    (net (code "43") (name "GPA1_2") (class "Default")
      (node (ref "IC7") (pin "22") (pinfunction "GPA1_22") (pintype "bidirectional"))
      (node (ref "SSW2") (pin "2") (pinfunction "SW2_2") (pintype "bidirectional"))
    )
    (net (code "44") (name "GPA2") (class "Default")
      (node (ref "B6") (pin "P$5") (pinfunction "SW2_P$5") (pintype "bidirectional"))
      (node (ref "B6ALT") (pin "P$5") (pinfunction "SW2_P$5") (pintype "bidirectional"))
      (node (ref "IC1") (pin "23") (pinfunction "GPA2_23") (pintype "bidirectional"))
    )
    (net (code "45") (name "GPA3") (class "Default")
      (node (ref "B5") (pin "P$5") (pinfunction "SW2_P$5") (pintype "bidirectional"))
      (node (ref "B5ALT") (pin "P$5") (pinfunction "SW2_P$5") (pintype "bidirectional"))
      (node (ref "IC1") (pin "24") (pinfunction "GPA3_24") (pintype "bidirectional"))
    )
    (net (code "46") (name "GPA4") (class "Default")
      (node (ref "B1") (pin "P$5") (pinfunction "SW2_P$5") (pintype "bidirectional"))
      (node (ref "B1ALT") (pin "P$5") (pinfunction "SW2_P$5") (pintype "bidirectional"))
      (node (ref "IC1") (pin "25") (pinfunction "GPA4_25") (pintype "bidirectional"))
    )
    (net (code "47") (name "GPA5") (class "Default")
      (node (ref "B2") (pin "P$5") (pinfunction "SW2_P$5") (pintype "bidirectional"))
      (node (ref "B2ALT") (pin "P$5") (pinfunction "SW2_P$5") (pintype "bidirectional"))
      (node (ref "IC1") (pin "26") (pinfunction "GPA5_26") (pintype "bidirectional"))
    )
    (net (code "48") (name "GPA6") (class "Default")
      (node (ref "B3") (pin "P$5") (pinfunction "SW2_P$5") (pintype "bidirectional"))
      (node (ref "B3ALT") (pin "P$5") (pinfunction "SW2_P$5") (pintype "bidirectional"))
      (node (ref "IC1") (pin "27") (pinfunction "GPA6_27") (pintype "bidirectional"))
    )
    (net (code "49") (name "GPA7") (class "Default")
      (node (ref "B4") (pin "P$5") (pinfunction "SW2_P$5") (pintype "bidirectional"))
      (node (ref "B4ALT") (pin "P$5") (pinfunction "SW2_P$5") (pintype "bidirectional"))
      (node (ref "IC1") (pin "28") (pinfunction "GPA7_28") (pintype "bidirectional"))
    )
    (net (code "50") (name "GPA8") (class "Default")
      (node (ref "B16") (pin "P$5") (pinfunction "SW2_P$5") (pintype "bidirectional"))
      (node (ref "IC1") (pin "1") (pinfunction "GPB0_1") (pintype "bidirectional"))
    )
    (net (code "51") (name "GPA9") (class "Default")
      (node (ref "B15") (pin "P$5") (pinfunction "SW2_P$5") (pintype "bidirectional"))
      (node (ref "IC1") (pin "2") (pinfunction "GPB1_2") (pintype "bidirectional"))
    )
    (net (code "52") (name "GPA10") (class "Default")
      (node (ref "B14") (pin "P$5") (pinfunction "SW2_P$5") (pintype "bidirectional"))
      (node (ref "B14ALT") (pin "P$5") (pinfunction "SW2_P$5") (pintype "bidirectional"))
      (node (ref "IC1") (pin "3") (pinfunction "GPB2_3") (pintype "bidirectional"))
    )
    (net (code "53") (name "GPA11") (class "Default")
      (node (ref "B13") (pin "P$5") (pinfunction "SW2_P$5") (pintype "bidirectional"))
      (node (ref "IC1") (pin "4") (pinfunction "GPB3_4") (pintype "bidirectional"))
    )
    (net (code "54") (name "GPA12") (class "Default")
      (node (ref "B9") (pin "P$5") (pinfunction "SW2_P$5") (pintype "bidirectional"))
      (node (ref "B9ALT") (pin "P$5") (pinfunction "SW2_P$5") (pintype "bidirectional"))
      (node (ref "IC1") (pin "5") (pinfunction "GPB4_5") (pintype "bidirectional"))
    )
    (net (code "55") (name "GPA13") (class "Default")
      (node (ref "B10") (pin "P$5") (pinfunction "SW2_P$5") (pintype "bidirectional"))
      (node (ref "B10ALT") (pin "P$5") (pinfunction "SW2_P$5") (pintype "bidirectional"))
      (node (ref "IC1") (pin "6") (pinfunction "GPB5_6") (pintype "bidirectional"))
    )
    (net (code "56") (name "GPA14") (class "Default")
      (node (ref "B11") (pin "P$5") (pinfunction "SW2_P$5") (pintype "bidirectional"))
      (node (ref "B11ALT") (pin "P$5") (pinfunction "SW2_P$5") (pintype "bidirectional"))
      (node (ref "IC1") (pin "7") (pinfunction "GPB6_7") (pintype "bidirectional"))
    )
    (net (code "57") (name "GPA15") (class "Default")
      (node (ref "B12") (pin "P$5") (pinfunction "SW2_P$5") (pintype "bidirectional"))
      (node (ref "B12ALT") (pin "P$5") (pinfunction "SW2_P$5") (pintype "bidirectional"))
      (node (ref "IC1") (pin "8") (pinfunction "GPB7_8") (pintype "bidirectional"))
    )
    (net (code "58") (name "GPA16") (class "Default")
      (node (ref "B24") (pin "P$5") (pinfunction "SW2_P$5") (pintype "bidirectional"))
      (node (ref "IC6") (pin "21") (pinfunction "GPA0_21") (pintype "bidirectional"))
    )
    (net (code "59") (name "GPA17") (class "Default")
      (node (ref "B23") (pin "P$5") (pinfunction "SW2_P$5") (pintype "bidirectional"))
      (node (ref "IC6") (pin "22") (pinfunction "GPA1_22") (pintype "bidirectional"))
    )
    (net (code "60") (name "GPA18") (class "Default")
      (node (ref "B22") (pin "P$5") (pinfunction "SW2_P$5") (pintype "bidirectional"))
      (node (ref "IC6") (pin "23") (pinfunction "GPA2_23") (pintype "bidirectional"))
    )
    (net (code "61") (name "GPA19") (class "Default")
      (node (ref "B21") (pin "P$5") (pinfunction "SW2_P$5") (pintype "bidirectional"))
      (node (ref "B21ALT") (pin "P$5") (pinfunction "SW2_P$5") (pintype "bidirectional"))
      (node (ref "IC6") (pin "24") (pinfunction "GPA3_24") (pintype "bidirectional"))
    )
    (net (code "62") (name "GPA20") (class "Default")
      (node (ref "B17") (pin "P$5") (pinfunction "SW2_P$5") (pintype "bidirectional"))
      (node (ref "B17ALT") (pin "P$5") (pinfunction "SW2_P$5") (pintype "bidirectional"))
      (node (ref "IC6") (pin "25") (pinfunction "GPA4_25") (pintype "bidirectional"))
    )
    (net (code "63") (name "GPA21") (class "Default")
      (node (ref "B18") (pin "P$5") (pinfunction "SW2_P$5") (pintype "bidirectional"))
      (node (ref "IC6") (pin "26") (pinfunction "GPA5_26") (pintype "bidirectional"))
    )
    (net (code "64") (name "GPA22") (class "Default")
      (node (ref "B19") (pin "P$5") (pinfunction "SW2_P$5") (pintype "bidirectional"))
      (node (ref "IC6") (pin "27") (pinfunction "GPA6_27") (pintype "bidirectional"))
    )
    (net (code "65") (name "GPA23") (class "Default")
      (node (ref "B20") (pin "P$5") (pinfunction "SW2_P$5") (pintype "bidirectional"))
      (node (ref "B20ALT") (pin "P$5") (pinfunction "SW2_P$5") (pintype "bidirectional"))
      (node (ref "IC6") (pin "28") (pinfunction "GPA7_28") (pintype "bidirectional"))
    )
    (net (code "66") (name "GPA24") (class "Default")
      (node (ref "IC6") (pin "1") (pinfunction "GPB0_1") (pintype "bidirectional"))
    )
    (net (code "67") (name "GPA25") (class "Default")
      (node (ref "IC6") (pin "2") (pinfunction "GPB1_2") (pintype "bidirectional"))
    )
    (net (code "68") (name "GPA26") (class "Default")
      (node (ref "B30") (pin "P$5") (pinfunction "SW2_P$5") (pintype "bidirectional"))
      (node (ref "IC6") (pin "3") (pinfunction "GPB2_3") (pintype "bidirectional"))
    )
    (net (code "69") (name "GPA27") (class "Default")
      (node (ref "B29") (pin "P$5") (pinfunction "SW2_P$5") (pintype "bidirectional"))
      (node (ref "IC6") (pin "4") (pinfunction "GPB3_4") (pintype "bidirectional"))
    )
    (net (code "70") (name "GPA28") (class "Default")
      (node (ref "B25") (pin "P$5") (pinfunction "SW2_P$5") (pintype "bidirectional"))
      (node (ref "IC6") (pin "5") (pinfunction "GPB4_5") (pintype "bidirectional"))
    )
    (net (code "71") (name "GPA29") (class "Default")
      (node (ref "B26") (pin "P$5") (pinfunction "SW2_P$5") (pintype "bidirectional"))
      (node (ref "B26ALT") (pin "P$5") (pinfunction "SW2_P$5") (pintype "bidirectional"))
      (node (ref "IC6") (pin "6") (pinfunction "GPB5_6") (pintype "bidirectional"))
    )
    (net (code "72") (name "GPA30") (class "Default")
      (node (ref "B27") (pin "P$5") (pinfunction "SW2_P$5") (pintype "bidirectional"))
      (node (ref "B27ALT") (pin "P$5") (pinfunction "SW2_P$5") (pintype "bidirectional"))
      (node (ref "IC6") (pin "7") (pinfunction "GPB6_7") (pintype "bidirectional"))
    )
    (net (code "73") (name "GPA31") (class "Default")
      (node (ref "B28") (pin "P$5") (pinfunction "SW2_P$5") (pintype "bidirectional"))
      (node (ref "IC6") (pin "8") (pinfunction "GPB7_8") (pintype "bidirectional"))
    )
    (net (code "74") (name "GPB0") (class "Default")
      (node (ref "IC7") (pin "1") (pinfunction "GPB0_1") (pintype "bidirectional"))
      (node (ref "SSW1") (pin "8") (pinfunction "SS_8") (pintype "bidirectional"))
    )
    (net (code "75") (name "GPB1") (class "Default")
      (node (ref "IC7") (pin "2") (pinfunction "GPB1_2") (pintype "bidirectional"))
      (node (ref "SSW2") (pin "8") (pinfunction "SS_8") (pintype "bidirectional"))
    )
    (net (code "76") (name "GPIO1-1") (class "Default")
      (node (ref "U1") (pin "33") (pinfunction "33_33") (pintype "bidirectional"))
    )
    (net (code "77") (name "GPIO1-2") (class "Default")
      (node (ref "U1") (pin "34") (pinfunction "34_34") (pintype "bidirectional"))
    )
    (net (code "78") (name "GPIO2-1") (class "Default")
      (node (ref "U1") (pin "38") (pinfunction "38_38") (pintype "bidirectional"))
    )
    (net (code "79") (name "GPIO2-2") (class "Default")
      (node (ref "U1") (pin "39") (pinfunction "39_39") (pintype "bidirectional"))
    )
    (net (code "80") (name "GPIO3-1") (class "Default")
      (node (ref "U1") (pin "40") (pinfunction "40_40") (pintype "bidirectional"))
    )
    (net (code "81") (name "GPIO3-2") (class "Default")
      (node (ref "U1") (pin "41") (pinfunction "41_41") (pintype "bidirectional"))
    )
    (net (code "82") (name "I2C_SCL") (class "Default")
      (node (ref "IC1") (pin "12") (pinfunction "SCL_12") (pintype "input"))
      (node (ref "IC2") (pin "26") (pinfunction "SCL_26") (pintype "input"))
      (node (ref "IC3") (pin "26") (pinfunction "SCL_26") (pintype "input"))
      (node (ref "IC4") (pin "26") (pinfunction "SCL_26") (pintype "input"))
      (node (ref "IC5") (pin "26") (pinfunction "SCL_26") (pintype "input"))
      (node (ref "IC6") (pin "12") (pinfunction "SCL_12") (pintype "input"))
      (node (ref "IC7") (pin "12") (pinfunction "SCL_12") (pintype "input"))
      (node (ref "IC8") (pin "12") (pinfunction "SCL_12") (pintype "input"))
      (node (ref "R5") (pin "1") (pinfunction "1_1") (pintype "passive"))
      (node (ref "SERIAL1") (pin "4") (pinfunction "4_4") (pintype "passive"))
      (node (ref "SERIAL2") (pin "4") (pinfunction "4_4") (pintype "passive"))
      (node (ref "SERIAL3") (pin "4") (pinfunction "4_4") (pintype "passive"))
      (node (ref "U1") (pin "21") (pinfunction "21(SCL)_21") (pintype "bidirectional"))
    )
    (net (code "83") (name "I2C_SDA") (class "Default")
      (node (ref "IC1") (pin "13") (pinfunction "SDA_13") (pintype "bidirectional"))
      (node (ref "IC2") (pin "27") (pinfunction "SDA_27") (pintype "input"))
      (node (ref "IC3") (pin "27") (pinfunction "SDA_27") (pintype "input"))
      (node (ref "IC4") (pin "27") (pinfunction "SDA_27") (pintype "input"))
      (node (ref "IC5") (pin "27") (pinfunction "SDA_27") (pintype "input"))
      (node (ref "IC6") (pin "13") (pinfunction "SDA_13") (pintype "bidirectional"))
      (node (ref "IC7") (pin "13") (pinfunction "SDA_13") (pintype "bidirectional"))
      (node (ref "IC8") (pin "13") (pinfunction "SDA_13") (pintype "bidirectional"))
      (node (ref "R6") (pin "1") (pinfunction "1_1") (pintype "passive"))
      (node (ref "SERIAL1") (pin "3") (pinfunction "3_3") (pintype "passive"))
      (node (ref "SERIAL2") (pin "3") (pinfunction "3_3") (pintype "passive"))
      (node (ref "SERIAL3") (pin "3") (pinfunction "3_3") (pintype "passive"))
      (node (ref "U1") (pin "20") (pinfunction "20(SDA)_20") (pintype "bidirectional"))
    )
    (net (code "84") (name "L0") (class "Default")
      (node (ref "B1") (pin "P$2") (pinfunction "K1_P$2") (pintype "bidirectional"))
      (node (ref "B1ALT") (pin "P$2") (pinfunction "K1_P$2") (pintype "bidirectional"))
      (node (ref "R23") (pin "1") (pinfunction "1_1") (pintype "passive"))
    )
    (net (code "85") (name "L1") (class "Default")
      (node (ref "B1") (pin "P$3") (pinfunction "K2_P$3") (pintype "bidirectional"))
      (node (ref "B1ALT") (pin "P$3") (pinfunction "K2_P$3") (pintype "bidirectional"))
      (node (ref "R22") (pin "1") (pinfunction "1_1") (pintype "passive"))
    )
    (net (code "86") (name "L2") (class "Default")
      (node (ref "B2") (pin "P$2") (pinfunction "K1_P$2") (pintype "bidirectional"))
      (node (ref "B2ALT") (pin "P$2") (pinfunction "K1_P$2") (pintype "bidirectional"))
      (node (ref "R21") (pin "1") (pinfunction "1_1") (pintype "passive"))
    )
    (net (code "87") (name "L3") (class "Default")
      (node (ref "B2") (pin "P$3") (pinfunction "K2_P$3") (pintype "bidirectional"))
      (node (ref "B2ALT") (pin "P$3") (pinfunction "K2_P$3") (pintype "bidirectional"))
      (node (ref "R20") (pin "1") (pinfunction "1_1") (pintype "passive"))
    )
    (net (code "88") (name "L4") (class "Default")
      (node (ref "B3") (pin "P$2") (pinfunction "K1_P$2") (pintype "bidirectional"))
      (node (ref "B3ALT") (pin "P$2") (pinfunction "K1_P$2") (pintype "bidirectional"))
      (node (ref "R19") (pin "1") (pinfunction "1_1") (pintype "passive"))
    )
    (net (code "89") (name "L5") (class "Default")
      (node (ref "B3") (pin "P$3") (pinfunction "K2_P$3") (pintype "bidirectional"))
      (node (ref "B3ALT") (pin "P$3") (pinfunction "K2_P$3") (pintype "bidirectional"))
      (node (ref "R18") (pin "1") (pinfunction "1_1") (pintype "passive"))
    )
    (net (code "90") (name "L6") (class "Default")
      (node (ref "B4") (pin "P$2") (pinfunction "K1_P$2") (pintype "bidirectional"))
      (node (ref "B4ALT") (pin "P$2") (pinfunction "K1_P$2") (pintype "bidirectional"))
      (node (ref "R17") (pin "1") (pinfunction "1_1") (pintype "passive"))
    )
    (net (code "91") (name "L7") (class "Default")
      (node (ref "B4") (pin "P$3") (pinfunction "K2_P$3") (pintype "bidirectional"))
      (node (ref "B4ALT") (pin "P$3") (pinfunction "K2_P$3") (pintype "bidirectional"))
      (node (ref "R16") (pin "1") (pinfunction "1_1") (pintype "passive"))
    )
    (net (code "92") (name "L8") (class "Default")
      (node (ref "B5") (pin "P$2") (pinfunction "K1_P$2") (pintype "bidirectional"))
      (node (ref "B5ALT") (pin "P$2") (pinfunction "K1_P$2") (pintype "bidirectional"))
      (node (ref "R15") (pin "1") (pinfunction "1_1") (pintype "passive"))
    )
    (net (code "93") (name "L9") (class "Default")
      (node (ref "B5") (pin "P$3") (pinfunction "K2_P$3") (pintype "bidirectional"))
      (node (ref "B5ALT") (pin "P$3") (pinfunction "K2_P$3") (pintype "bidirectional"))
      (node (ref "R14") (pin "1") (pinfunction "1_1") (pintype "passive"))
    )
    (net (code "94") (name "L10") (class "Default")
      (node (ref "B6") (pin "P$2") (pinfunction "K1_P$2") (pintype "bidirectional"))
      (node (ref "B6ALT") (pin "P$2") (pinfunction "K1_P$2") (pintype "bidirectional"))
      (node (ref "R13") (pin "1") (pinfunction "1_1") (pintype "passive"))
    )
    (net (code "95") (name "L11") (class "Default")
      (node (ref "B6") (pin "P$3") (pinfunction "K2_P$3") (pintype "bidirectional"))
      (node (ref "B6ALT") (pin "P$3") (pinfunction "K2_P$3") (pintype "bidirectional"))
      (node (ref "R12") (pin "1") (pinfunction "1_1") (pintype "passive"))
    )
    (net (code "96") (name "L12") (class "Default")
      (node (ref "B7") (pin "P$2") (pinfunction "K1_P$2") (pintype "bidirectional"))
      (node (ref "B7ALT") (pin "P$2") (pinfunction "K1_P$2") (pintype "bidirectional"))
      (node (ref "R11") (pin "1") (pinfunction "1_1") (pintype "passive"))
    )
    (net (code "97") (name "L13") (class "Default")
      (node (ref "B7") (pin "P$3") (pinfunction "K2_P$3") (pintype "bidirectional"))
      (node (ref "B7ALT") (pin "P$3") (pinfunction "K2_P$3") (pintype "bidirectional"))
      (node (ref "R10") (pin "1") (pinfunction "1_1") (pintype "passive"))
    )
    (net (code "98") (name "L14") (class "Default")
      (node (ref "B8") (pin "P$2") (pinfunction "K1_P$2") (pintype "bidirectional"))
      (node (ref "B8ALT") (pin "P$2") (pinfunction "K1_P$2") (pintype "bidirectional"))
      (node (ref "R4") (pin "1") (pinfunction "1_1") (pintype "passive"))
    )
    (net (code "99") (name "L15") (class "Default")
      (node (ref "B8") (pin "P$3") (pinfunction "K2_P$3") (pintype "bidirectional"))
      (node (ref "B8ALT") (pin "P$3") (pinfunction "K2_P$3") (pintype "bidirectional"))
      (node (ref "R3") (pin "1") (pinfunction "1_1") (pintype "passive"))
    )
    (net (code "100") (name "L16") (class "Default")
      (node (ref "B9") (pin "P$2") (pinfunction "K1_P$2") (pintype "bidirectional"))
      (node (ref "B9ALT") (pin "P$2") (pinfunction "K1_P$2") (pintype "bidirectional"))
      (node (ref "R39") (pin "1") (pinfunction "1_1") (pintype "passive"))
    )
    (net (code "101") (name "L17") (class "Default")
      (node (ref "B9") (pin "P$3") (pinfunction "K2_P$3") (pintype "bidirectional"))
      (node (ref "B9ALT") (pin "P$3") (pinfunction "K2_P$3") (pintype "bidirectional"))
      (node (ref "R38") (pin "1") (pinfunction "1_1") (pintype "passive"))
    )
    (net (code "102") (name "L18") (class "Default")
      (node (ref "B10") (pin "P$2") (pinfunction "K1_P$2") (pintype "bidirectional"))
      (node (ref "B10ALT") (pin "P$2") (pinfunction "K1_P$2") (pintype "bidirectional"))
      (node (ref "R37") (pin "1") (pinfunction "1_1") (pintype "passive"))
    )
    (net (code "103") (name "L19") (class "Default")
      (node (ref "B10") (pin "P$3") (pinfunction "K2_P$3") (pintype "bidirectional"))
      (node (ref "B10ALT") (pin "P$3") (pinfunction "K2_P$3") (pintype "bidirectional"))
      (node (ref "R36") (pin "1") (pinfunction "1_1") (pintype "passive"))
    )
    (net (code "104") (name "L20") (class "Default")
      (node (ref "B11") (pin "P$2") (pinfunction "K1_P$2") (pintype "bidirectional"))
      (node (ref "B11ALT") (pin "P$2") (pinfunction "K1_P$2") (pintype "bidirectional"))
      (node (ref "R35") (pin "1") (pinfunction "1_1") (pintype "passive"))
    )
    (net (code "105") (name "L21") (class "Default")
      (node (ref "B11") (pin "P$3") (pinfunction "K2_P$3") (pintype "bidirectional"))
      (node (ref "B11ALT") (pin "P$3") (pinfunction "K2_P$3") (pintype "bidirectional"))
      (node (ref "R34") (pin "1") (pinfunction "1_1") (pintype "passive"))
    )
    (net (code "106") (name "L22") (class "Default")
      (node (ref "B12") (pin "P$2") (pinfunction "K1_P$2") (pintype "bidirectional"))
      (node (ref "B12ALT") (pin "P$2") (pinfunction "K1_P$2") (pintype "bidirectional"))
      (node (ref "R33") (pin "1") (pinfunction "1_1") (pintype "passive"))
    )
    (net (code "107") (name "L23") (class "Default")
      (node (ref "B12") (pin "P$3") (pinfunction "K2_P$3") (pintype "bidirectional"))
      (node (ref "B12ALT") (pin "P$3") (pinfunction "K2_P$3") (pintype "bidirectional"))
      (node (ref "R32") (pin "1") (pinfunction "1_1") (pintype "passive"))
    )
    (net (code "108") (name "L24") (class "Default")
      (node (ref "B13") (pin "P$2") (pinfunction "K1_P$2") (pintype "bidirectional"))
      (node (ref "R31") (pin "1") (pinfunction "1_1") (pintype "passive"))
    )
    (net (code "109") (name "L25") (class "Default")
      (node (ref "B13") (pin "P$3") (pinfunction "K2_P$3") (pintype "bidirectional"))
      (node (ref "R30") (pin "1") (pinfunction "1_1") (pintype "passive"))
    )
    (net (code "110") (name "L26") (class "Default")
      (node (ref "B14") (pin "P$2") (pinfunction "K1_P$2") (pintype "bidirectional"))
      (node (ref "B14ALT") (pin "P$2") (pinfunction "K1_P$2") (pintype "bidirectional"))
      (node (ref "R29") (pin "1") (pinfunction "1_1") (pintype "passive"))
    )
    (net (code "111") (name "L27") (class "Default")
      (node (ref "B14") (pin "P$3") (pinfunction "K2_P$3") (pintype "bidirectional"))
      (node (ref "B14ALT") (pin "P$3") (pinfunction "K2_P$3") (pintype "bidirectional"))
      (node (ref "R28") (pin "1") (pinfunction "1_1") (pintype "passive"))
    )
    (net (code "112") (name "L28") (class "Default")
      (node (ref "B15") (pin "P$2") (pinfunction "K1_P$2") (pintype "bidirectional"))
      (node (ref "R27") (pin "1") (pinfunction "1_1") (pintype "passive"))
    )
    (net (code "113") (name "L29") (class "Default")
      (node (ref "B15") (pin "P$3") (pinfunction "K2_P$3") (pintype "bidirectional"))
      (node (ref "R26") (pin "1") (pinfunction "1_1") (pintype "passive"))
    )
    (net (code "114") (name "L30") (class "Default")
      (node (ref "B16") (pin "P$2") (pinfunction "K1_P$2") (pintype "bidirectional"))
      (node (ref "R25") (pin "1") (pinfunction "1_1") (pintype "passive"))
    )
    (net (code "115") (name "L31") (class "Default")
      (node (ref "B16") (pin "P$3") (pinfunction "K2_P$3") (pintype "bidirectional"))
      (node (ref "R24") (pin "1") (pinfunction "1_1") (pintype "passive"))
    )
    (net (code "116") (name "L32") (class "Default")
      (node (ref "B17") (pin "P$2") (pinfunction "K1_P$2") (pintype "bidirectional"))
      (node (ref "B17ALT") (pin "P$2") (pinfunction "K1_P$2") (pintype "bidirectional"))
      (node (ref "R55") (pin "1") (pinfunction "1_1") (pintype "passive"))
    )
    (net (code "117") (name "L33") (class "Default")
      (node (ref "B17") (pin "P$3") (pinfunction "K2_P$3") (pintype "bidirectional"))
      (node (ref "B17ALT") (pin "P$3") (pinfunction "K2_P$3") (pintype "bidirectional"))
      (node (ref "R54") (pin "1") (pinfunction "1_1") (pintype "passive"))
    )
    (net (code "118") (name "L34") (class "Default")
      (node (ref "B18") (pin "P$2") (pinfunction "K1_P$2") (pintype "bidirectional"))
      (node (ref "R53") (pin "1") (pinfunction "1_1") (pintype "passive"))
    )
    (net (code "119") (name "L35") (class "Default")
      (node (ref "B18") (pin "P$3") (pinfunction "K2_P$3") (pintype "bidirectional"))
      (node (ref "R52") (pin "1") (pinfunction "1_1") (pintype "passive"))
    )
    (net (code "120") (name "L36") (class "Default")
      (node (ref "B19") (pin "P$2") (pinfunction "K1_P$2") (pintype "bidirectional"))
      (node (ref "R51") (pin "1") (pinfunction "1_1") (pintype "passive"))
    )
    (net (code "121") (name "L37") (class "Default")
      (node (ref "B19") (pin "P$3") (pinfunction "K2_P$3") (pintype "bidirectional"))
      (node (ref "R50") (pin "1") (pinfunction "1_1") (pintype "passive"))
    )
    (net (code "122") (name "L38") (class "Default")
      (node (ref "B20") (pin "P$2") (pinfunction "K1_P$2") (pintype "bidirectional"))
      (node (ref "B20ALT") (pin "P$2") (pinfunction "K1_P$2") (pintype "bidirectional"))
      (node (ref "R49") (pin "1") (pinfunction "1_1") (pintype "passive"))
    )
    (net (code "123") (name "L39") (class "Default")
      (node (ref "B20") (pin "P$3") (pinfunction "K2_P$3") (pintype "bidirectional"))
      (node (ref "B20ALT") (pin "P$3") (pinfunction "K2_P$3") (pintype "bidirectional"))
      (node (ref "R48") (pin "1") (pinfunction "1_1") (pintype "passive"))
    )
    (net (code "124") (name "L40") (class "Default")
      (node (ref "B21") (pin "P$2") (pinfunction "K1_P$2") (pintype "bidirectional"))
      (node (ref "B21ALT") (pin "P$2") (pinfunction "K1_P$2") (pintype "bidirectional"))
      (node (ref "R47") (pin "1") (pinfunction "1_1") (pintype "passive"))
    )
    (net (code "125") (name "L41") (class "Default")
      (node (ref "B21") (pin "P$3") (pinfunction "K2_P$3") (pintype "bidirectional"))
      (node (ref "B21ALT") (pin "P$3") (pinfunction "K2_P$3") (pintype "bidirectional"))
      (node (ref "R46") (pin "1") (pinfunction "1_1") (pintype "passive"))
    )
    (net (code "126") (name "L42") (class "Default")
      (node (ref "B22") (pin "P$2") (pinfunction "K1_P$2") (pintype "bidirectional"))
      (node (ref "R45") (pin "1") (pinfunction "1_1") (pintype "passive"))
    )
    (net (code "127") (name "L43") (class "Default")
      (node (ref "B22") (pin "P$3") (pinfunction "K2_P$3") (pintype "bidirectional"))
      (node (ref "R44") (pin "1") (pinfunction "1_1") (pintype "passive"))
    )
    (net (code "128") (name "L44") (class "Default")
      (node (ref "B23") (pin "P$2") (pinfunction "K1_P$2") (pintype "bidirectional"))
      (node (ref "R43") (pin "1") (pinfunction "1_1") (pintype "passive"))
    )
    (net (code "129") (name "L45") (class "Default")
      (node (ref "B23") (pin "P$3") (pinfunction "K2_P$3") (pintype "bidirectional"))
      (node (ref "R42") (pin "1") (pinfunction "1_1") (pintype "passive"))
    )
    (net (code "130") (name "L46") (class "Default")
      (node (ref "B24") (pin "P$2") (pinfunction "K1_P$2") (pintype "bidirectional"))
      (node (ref "R41") (pin "1") (pinfunction "1_1") (pintype "passive"))
    )
    (net (code "131") (name "L47") (class "Default")
      (node (ref "B24") (pin "P$3") (pinfunction "K2_P$3") (pintype "bidirectional"))
      (node (ref "R40") (pin "1") (pinfunction "1_1") (pintype "passive"))
    )
    (net (code "132") (name "L48") (class "Default")
      (node (ref "B25") (pin "P$2") (pinfunction "K1_P$2") (pintype "bidirectional"))
      (node (ref "R71") (pin "1") (pinfunction "1_1") (pintype "passive"))
    )
    (net (code "133") (name "L49") (class "Default")
      (node (ref "B25") (pin "P$3") (pinfunction "K2_P$3") (pintype "bidirectional"))
      (node (ref "R70") (pin "1") (pinfunction "1_1") (pintype "passive"))
    )
    (net (code "134") (name "L50") (class "Default")
      (node (ref "B26") (pin "P$2") (pinfunction "K1_P$2") (pintype "bidirectional"))
      (node (ref "B26ALT") (pin "P$2") (pinfunction "K1_P$2") (pintype "bidirectional"))
      (node (ref "R69") (pin "1") (pinfunction "1_1") (pintype "passive"))
    )
    (net (code "135") (name "L51") (class "Default")
      (node (ref "B26") (pin "P$3") (pinfunction "K2_P$3") (pintype "bidirectional"))
      (node (ref "B26ALT") (pin "P$3") (pinfunction "K2_P$3") (pintype "bidirectional"))
      (node (ref "R68") (pin "1") (pinfunction "1_1") (pintype "passive"))
    )
    (net (code "136") (name "L52") (class "Default")
      (node (ref "B27") (pin "P$2") (pinfunction "K1_P$2") (pintype "bidirectional"))
      (node (ref "B27ALT") (pin "P$2") (pinfunction "K1_P$2") (pintype "bidirectional"))
      (node (ref "R67") (pin "1") (pinfunction "1_1") (pintype "passive"))
    )
    (net (code "137") (name "L53") (class "Default")
      (node (ref "B27") (pin "P$3") (pinfunction "K2_P$3") (pintype "bidirectional"))
      (node (ref "B27ALT") (pin "P$3") (pinfunction "K2_P$3") (pintype "bidirectional"))
      (node (ref "R66") (pin "1") (pinfunction "1_1") (pintype "passive"))
    )
    (net (code "138") (name "L54") (class "Default")
      (node (ref "B28") (pin "P$2") (pinfunction "K1_P$2") (pintype "bidirectional"))
      (node (ref "R65") (pin "1") (pinfunction "1_1") (pintype "passive"))
    )
    (net (code "139") (name "L55") (class "Default")
      (node (ref "B28") (pin "P$3") (pinfunction "K2_P$3") (pintype "bidirectional"))
      (node (ref "R64") (pin "1") (pinfunction "1_1") (pintype "passive"))
    )
    (net (code "140") (name "L56") (class "Default")
      (node (ref "B29") (pin "P$2") (pinfunction "K1_P$2") (pintype "bidirectional"))
      (node (ref "R63") (pin "1") (pinfunction "1_1") (pintype "passive"))
    )
    (net (code "141") (name "L57") (class "Default")
      (node (ref "B29") (pin "P$3") (pinfunction "K2_P$3") (pintype "bidirectional"))
      (node (ref "R62") (pin "1") (pinfunction "1_1") (pintype "passive"))
    )
    (net (code "142") (name "L58") (class "Default")
      (node (ref "B30") (pin "P$2") (pinfunction "K1_P$2") (pintype "bidirectional"))
      (node (ref "R61") (pin "1") (pinfunction "1_1") (pintype "passive"))
    )
    (net (code "143") (name "L59") (class "Default")
      (node (ref "B30") (pin "P$3") (pinfunction "K2_P$3") (pintype "bidirectional"))
      (node (ref "R60") (pin "1") (pinfunction "1_1") (pintype "passive"))
    )
    (net (code "144") (name "MOSI") (class "Default")
      (node (ref "C2") (pin "1") (pinfunction "1_1") (pintype "passive"))
      (node (ref "R2") (pin "1") (pinfunction "1_1") (pintype "passive"))
      (node (ref "SERIAL1") (pin "8") (pinfunction "8_8") (pintype "passive"))
      (node (ref "SERIAL2") (pin "8") (pinfunction "8_8") (pintype "passive"))
      (node (ref "SERIAL3") (pin "8") (pinfunction "8_8") (pintype "passive"))
      (node (ref "SSW1") (pin "6") (pinfunction "SDI_6") (pintype "bidirectional"))
      (node (ref "SSW2") (pin "6") (pinfunction "SDI_6") (pintype "bidirectional"))
    )
    (net (code "145") (name "N$18") (class "Default")
      (node (ref "U1") (pin "53") (pinfunction "53_53") (pintype "bidirectional"))
    )
    (net (code "146") (name "N$19") (class "Default")
      (node (ref "U1") (pin "52") (pinfunction "52_52") (pintype "bidirectional"))
    )
    (net (code "147") (name "N$20") (class "Default")
      (node (ref "U1") (pin "51") (pinfunction "51_51") (pintype "bidirectional"))
    )
    (net (code "148") (name "N$21") (class "Default")
      (node (ref "U1") (pin "50") (pinfunction "50_50") (pintype "bidirectional"))
    )
    (net (code "149") (name "N$24") (class "Default")
      (node (ref "U1") (pin "47") (pinfunction "47_47") (pintype "bidirectional"))
    )
    (net (code "150") (name "N$25") (class "Default")
      (node (ref "U1") (pin "46") (pinfunction "46_46") (pintype "bidirectional"))
    )
    (net (code "151") (name "N$26") (class "Default")
      (node (ref "U1") (pin "45") (pinfunction "45_45") (pintype "bidirectional"))
    )
    (net (code "152") (name "N$27") (class "Default")
      (node (ref "U1") (pin "44") (pinfunction "44_44") (pintype "bidirectional"))
    )
    (net (code "153") (name "N$28") (class "Default")
      (node (ref "U1") (pin "43") (pinfunction "43_43") (pintype "bidirectional"))
    )
    (net (code "154") (name "N$29") (class "Default")
      (node (ref "U1") (pin "42") (pinfunction "42_42") (pintype "bidirectional"))
    )
    (net (code "155") (name "Net-(IC2-L0)") (class "Default")
      (node (ref "IC2") (pin "6") (pinfunction "L0_6") (pintype "output"))
      (node (ref "R23") (pin "2") (pinfunction "2_2") (pintype "passive"))
    )
    (net (code "156") (name "Net-(IC2-L1)") (class "Default")
      (node (ref "IC2") (pin "7") (pinfunction "L1_7") (pintype "output"))
      (node (ref "R22") (pin "2") (pinfunction "2_2") (pintype "passive"))
    )
    (net (code "157") (name "Net-(IC2-L2)") (class "Default")
      (node (ref "IC2") (pin "8") (pinfunction "L2_8") (pintype "output"))
      (node (ref "R21") (pin "2") (pinfunction "2_2") (pintype "passive"))
    )
    (net (code "158") (name "Net-(IC2-L3)") (class "Default")
      (node (ref "IC2") (pin "9") (pinfunction "L3_9") (pintype "output"))
      (node (ref "R20") (pin "2") (pinfunction "2_2") (pintype "passive"))
    )
    (net (code "159") (name "Net-(IC2-L4)") (class "Default")
      (node (ref "IC2") (pin "10") (pinfunction "L4_10") (pintype "output"))
      (node (ref "R19") (pin "2") (pinfunction "2_2") (pintype "passive"))
    )
    (net (code "160") (name "Net-(IC2-L5)") (class "Default")
      (node (ref "IC2") (pin "11") (pinfunction "L5_11") (pintype "output"))
      (node (ref "R18") (pin "2") (pinfunction "2_2") (pintype "passive"))
    )
    (net (code "161") (name "Net-(IC2-L6)") (class "Default")
      (node (ref "IC2") (pin "12") (pinfunction "L6_12") (pintype "output"))
      (node (ref "R17") (pin "2") (pinfunction "2_2") (pintype "passive"))
    )
    (net (code "162") (name "Net-(IC2-L7)") (class "Default")
      (node (ref "IC2") (pin "13") (pinfunction "L7_13") (pintype "output"))
      (node (ref "R16") (pin "2") (pinfunction "2_2") (pintype "passive"))
    )
    (net (code "163") (name "Net-(IC2-L8)") (class "Default")
      (node (ref "IC2") (pin "15") (pinfunction "L8_15") (pintype "output"))
      (node (ref "R15") (pin "2") (pinfunction "2_2") (pintype "passive"))
    )
    (net (code "164") (name "Net-(IC2-L9)") (class "Default")
      (node (ref "IC2") (pin "16") (pinfunction "L9_16") (pintype "output"))
      (node (ref "R14") (pin "2") (pinfunction "2_2") (pintype "passive"))
    )
    (net (code "165") (name "Net-(IC2-L10)") (class "Default")
      (node (ref "IC2") (pin "17") (pinfunction "L10_17") (pintype "output"))
      (node (ref "R13") (pin "2") (pinfunction "2_2") (pintype "passive"))
    )
    (net (code "166") (name "Net-(IC2-L11)") (class "Default")
      (node (ref "IC2") (pin "18") (pinfunction "L11_18") (pintype "output"))
      (node (ref "R12") (pin "2") (pinfunction "2_2") (pintype "passive"))
    )
    (net (code "167") (name "Net-(IC2-L12)") (class "Default")
      (node (ref "IC2") (pin "19") (pinfunction "L12_19") (pintype "output"))
      (node (ref "R11") (pin "2") (pinfunction "2_2") (pintype "passive"))
    )
    (net (code "168") (name "Net-(IC2-L13)") (class "Default")
      (node (ref "IC2") (pin "20") (pinfunction "L13_20") (pintype "output"))
      (node (ref "R10") (pin "2") (pinfunction "2_2") (pintype "passive"))
    )
    (net (code "169") (name "Net-(IC2-L14)") (class "Default")
      (node (ref "IC2") (pin "21") (pinfunction "L14_21") (pintype "output"))
      (node (ref "R4") (pin "2") (pinfunction "2_2") (pintype "passive"))
    )
    (net (code "170") (name "Net-(IC2-L15)") (class "Default")
      (node (ref "IC2") (pin "22") (pinfunction "L15_22") (pintype "output"))
      (node (ref "R3") (pin "2") (pinfunction "2_2") (pintype "passive"))
    )
    (net (code "171") (name "Net-(IC3-L0)") (class "Default")
      (node (ref "IC3") (pin "6") (pinfunction "L0_6") (pintype "output"))
      (node (ref "R39") (pin "2") (pinfunction "2_2") (pintype "passive"))
    )
    (net (code "172") (name "Net-(IC3-L1)") (class "Default")
      (node (ref "IC3") (pin "7") (pinfunction "L1_7") (pintype "output"))
      (node (ref "R38") (pin "2") (pinfunction "2_2") (pintype "passive"))
    )
    (net (code "173") (name "Net-(IC3-L2)") (class "Default")
      (node (ref "IC3") (pin "8") (pinfunction "L2_8") (pintype "output"))
      (node (ref "R37") (pin "2") (pinfunction "2_2") (pintype "passive"))
    )
    (net (code "174") (name "Net-(IC3-L3)") (class "Default")
      (node (ref "IC3") (pin "9") (pinfunction "L3_9") (pintype "output"))
      (node (ref "R36") (pin "2") (pinfunction "2_2") (pintype "passive"))
    )
    (net (code "175") (name "Net-(IC3-L4)") (class "Default")
      (node (ref "IC3") (pin "10") (pinfunction "L4_10") (pintype "output"))
      (node (ref "R35") (pin "2") (pinfunction "2_2") (pintype "passive"))
    )
    (net (code "176") (name "Net-(IC3-L5)") (class "Default")
      (node (ref "IC3") (pin "11") (pinfunction "L5_11") (pintype "output"))
      (node (ref "R34") (pin "2") (pinfunction "2_2") (pintype "passive"))
    )
    (net (code "177") (name "Net-(IC3-L6)") (class "Default")
      (node (ref "IC3") (pin "12") (pinfunction "L6_12") (pintype "output"))
      (node (ref "R33") (pin "2") (pinfunction "2_2") (pintype "passive"))
    )
    (net (code "178") (name "Net-(IC3-L7)") (class "Default")
      (node (ref "IC3") (pin "13") (pinfunction "L7_13") (pintype "output"))
      (node (ref "R32") (pin "2") (pinfunction "2_2") (pintype "passive"))
    )
    (net (code "179") (name "Net-(IC3-L8)") (class "Default")
      (node (ref "IC3") (pin "15") (pinfunction "L8_15") (pintype "output"))
      (node (ref "R31") (pin "2") (pinfunction "2_2") (pintype "passive"))
    )
    (net (code "180") (name "Net-(IC3-L9)") (class "Default")
      (node (ref "IC3") (pin "16") (pinfunction "L9_16") (pintype "output"))
      (node (ref "R30") (pin "2") (pinfunction "2_2") (pintype "passive"))
    )
    (net (code "181") (name "Net-(IC3-L10)") (class "Default")
      (node (ref "IC3") (pin "17") (pinfunction "L10_17") (pintype "output"))
      (node (ref "R29") (pin "2") (pinfunction "2_2") (pintype "passive"))
    )
    (net (code "182") (name "Net-(IC3-L11)") (class "Default")
      (node (ref "IC3") (pin "18") (pinfunction "L11_18") (pintype "output"))
      (node (ref "R28") (pin "2") (pinfunction "2_2") (pintype "passive"))
    )
    (net (code "183") (name "Net-(IC3-L12)") (class "Default")
      (node (ref "IC3") (pin "19") (pinfunction "L12_19") (pintype "output"))
      (node (ref "R27") (pin "2") (pinfunction "2_2") (pintype "passive"))
    )
    (net (code "184") (name "Net-(IC3-L13)") (class "Default")
      (node (ref "IC3") (pin "20") (pinfunction "L13_20") (pintype "output"))
      (node (ref "R26") (pin "2") (pinfunction "2_2") (pintype "passive"))
    )
    (net (code "185") (name "Net-(IC3-L14)") (class "Default")
      (node (ref "IC3") (pin "21") (pinfunction "L14_21") (pintype "output"))
      (node (ref "R25") (pin "2") (pinfunction "2_2") (pintype "passive"))
    )
    (net (code "186") (name "Net-(IC3-L15)") (class "Default")
      (node (ref "IC3") (pin "22") (pinfunction "L15_22") (pintype "output"))
      (node (ref "R24") (pin "2") (pinfunction "2_2") (pintype "passive"))
    )
    (net (code "187") (name "Net-(IC4-L0)") (class "Default")
      (node (ref "IC4") (pin "6") (pinfunction "L0_6") (pintype "output"))
      (node (ref "R55") (pin "2") (pinfunction "2_2") (pintype "passive"))
    )
    (net (code "188") (name "Net-(IC4-L1)") (class "Default")
      (node (ref "IC4") (pin "7") (pinfunction "L1_7") (pintype "output"))
      (node (ref "R54") (pin "2") (pinfunction "2_2") (pintype "passive"))
    )
    (net (code "189") (name "Net-(IC4-L2)") (class "Default")
      (node (ref "IC4") (pin "8") (pinfunction "L2_8") (pintype "output"))
      (node (ref "R53") (pin "2") (pinfunction "2_2") (pintype "passive"))
    )
    (net (code "190") (name "Net-(IC4-L3)") (class "Default")
      (node (ref "IC4") (pin "9") (pinfunction "L3_9") (pintype "output"))
      (node (ref "R52") (pin "2") (pinfunction "2_2") (pintype "passive"))
    )
    (net (code "191") (name "Net-(IC4-L4)") (class "Default")
      (node (ref "IC4") (pin "10") (pinfunction "L4_10") (pintype "output"))
      (node (ref "R51") (pin "2") (pinfunction "2_2") (pintype "passive"))
    )
    (net (code "192") (name "Net-(IC4-L5)") (class "Default")
      (node (ref "IC4") (pin "11") (pinfunction "L5_11") (pintype "output"))
      (node (ref "R50") (pin "2") (pinfunction "2_2") (pintype "passive"))
    )
    (net (code "193") (name "Net-(IC4-L6)") (class "Default")
      (node (ref "IC4") (pin "12") (pinfunction "L6_12") (pintype "output"))
      (node (ref "R49") (pin "2") (pinfunction "2_2") (pintype "passive"))
    )
    (net (code "194") (name "Net-(IC4-L7)") (class "Default")
      (node (ref "IC4") (pin "13") (pinfunction "L7_13") (pintype "output"))
      (node (ref "R48") (pin "2") (pinfunction "2_2") (pintype "passive"))
    )
    (net (code "195") (name "Net-(IC4-L8)") (class "Default")
      (node (ref "IC4") (pin "15") (pinfunction "L8_15") (pintype "output"))
      (node (ref "R47") (pin "2") (pinfunction "2_2") (pintype "passive"))
    )
    (net (code "196") (name "Net-(IC4-L9)") (class "Default")
      (node (ref "IC4") (pin "16") (pinfunction "L9_16") (pintype "output"))
      (node (ref "R46") (pin "2") (pinfunction "2_2") (pintype "passive"))
    )
    (net (code "197") (name "Net-(IC4-L10)") (class "Default")
      (node (ref "IC4") (pin "17") (pinfunction "L10_17") (pintype "output"))
      (node (ref "R45") (pin "2") (pinfunction "2_2") (pintype "passive"))
    )
    (net (code "198") (name "Net-(IC4-L11)") (class "Default")
      (node (ref "IC4") (pin "18") (pinfunction "L11_18") (pintype "output"))
      (node (ref "R44") (pin "2") (pinfunction "2_2") (pintype "passive"))
    )
    (net (code "199") (name "Net-(IC4-L12)") (class "Default")
      (node (ref "IC4") (pin "19") (pinfunction "L12_19") (pintype "output"))
      (node (ref "R43") (pin "2") (pinfunction "2_2") (pintype "passive"))
    )
    (net (code "200") (name "Net-(IC4-L13)") (class "Default")
      (node (ref "IC4") (pin "20") (pinfunction "L13_20") (pintype "output"))
      (node (ref "R42") (pin "2") (pinfunction "2_2") (pintype "passive"))
    )
    (net (code "201") (name "Net-(IC4-L14)") (class "Default")
      (node (ref "IC4") (pin "21") (pinfunction "L14_21") (pintype "output"))
      (node (ref "R41") (pin "2") (pinfunction "2_2") (pintype "passive"))
    )
    (net (code "202") (name "Net-(IC4-L15)") (class "Default")
      (node (ref "IC4") (pin "22") (pinfunction "L15_22") (pintype "output"))
      (node (ref "R40") (pin "2") (pinfunction "2_2") (pintype "passive"))
    )
    (net (code "203") (name "Net-(IC5-L0)") (class "Default")
      (node (ref "IC5") (pin "6") (pinfunction "L0_6") (pintype "output"))
      (node (ref "R71") (pin "2") (pinfunction "2_2") (pintype "passive"))
    )
    (net (code "204") (name "Net-(IC5-L1)") (class "Default")
      (node (ref "IC5") (pin "7") (pinfunction "L1_7") (pintype "output"))
      (node (ref "R70") (pin "2") (pinfunction "2_2") (pintype "passive"))
    )
    (net (code "205") (name "Net-(IC5-L2)") (class "Default")
      (node (ref "IC5") (pin "8") (pinfunction "L2_8") (pintype "output"))
      (node (ref "R69") (pin "2") (pinfunction "2_2") (pintype "passive"))
    )
    (net (code "206") (name "Net-(IC5-L3)") (class "Default")
      (node (ref "IC5") (pin "9") (pinfunction "L3_9") (pintype "output"))
      (node (ref "R68") (pin "2") (pinfunction "2_2") (pintype "passive"))
    )
    (net (code "207") (name "Net-(IC5-L4)") (class "Default")
      (node (ref "IC5") (pin "10") (pinfunction "L4_10") (pintype "output"))
      (node (ref "R67") (pin "2") (pinfunction "2_2") (pintype "passive"))
    )
    (net (code "208") (name "Net-(IC5-L5)") (class "Default")
      (node (ref "IC5") (pin "11") (pinfunction "L5_11") (pintype "output"))
      (node (ref "R66") (pin "2") (pinfunction "2_2") (pintype "passive"))
    )
    (net (code "209") (name "Net-(IC5-L6)") (class "Default")
      (node (ref "IC5") (pin "12") (pinfunction "L6_12") (pintype "output"))
      (node (ref "R65") (pin "2") (pinfunction "2_2") (pintype "passive"))
    )
    (net (code "210") (name "Net-(IC5-L7)") (class "Default")
      (node (ref "IC5") (pin "13") (pinfunction "L7_13") (pintype "output"))
      (node (ref "R64") (pin "2") (pinfunction "2_2") (pintype "passive"))
    )
    (net (code "211") (name "Net-(IC5-L8)") (class "Default")
      (node (ref "IC5") (pin "15") (pinfunction "L8_15") (pintype "output"))
      (node (ref "R63") (pin "2") (pinfunction "2_2") (pintype "passive"))
    )
    (net (code "212") (name "Net-(IC5-L9)") (class "Default")
      (node (ref "IC5") (pin "16") (pinfunction "L9_16") (pintype "output"))
      (node (ref "R62") (pin "2") (pinfunction "2_2") (pintype "passive"))
    )
    (net (code "213") (name "Net-(IC5-L10)") (class "Default")
      (node (ref "IC5") (pin "17") (pinfunction "L10_17") (pintype "output"))
      (node (ref "R61") (pin "2") (pinfunction "2_2") (pintype "passive"))
    )
    (net (code "214") (name "Net-(IC5-L11)") (class "Default")
      (node (ref "IC5") (pin "18") (pinfunction "L11_18") (pintype "output"))
      (node (ref "R60") (pin "2") (pinfunction "2_2") (pintype "passive"))
    )
    (net (code "215") (name "Net-(IC9A-I)") (class "Default")
      (node (ref "C24") (pin "1") (pinfunction "1_1") (pintype "passive"))
      (node (ref "IC9") (pin "13") (pinfunction "I_13") (pintype "input"))
      (node (ref "R56") (pin "1") (pinfunction "1_1") (pintype "passive"))
    )
    (net (code "216") (name "Net-(JOYSTICKS-Pad7)") (class "Default")
      (node (ref "JOYSTICKS") (pin "7") (pinfunction "7_7") (pintype "passive"))
      (node (ref "L6") (pin "2") (pinfunction "2_2") (pintype "passive"))
    )
    (net (code "217") (name "Net-(L1-Pad2)") (class "Default")
      (node (ref "L1") (pin "2") (pinfunction "2_2") (pintype "passive"))
      (node (ref "SJ1") (pin "2") (pinfunction "2_2") (pintype "passive"))
      (node (ref "SJ2") (pin "1") (pinfunction "1_1") (pintype "passive"))
    )
    (net (code "218") (name "Net-(L2-Pad1)") (class "Default")
      (node (ref "L2") (pin "1") (pinfunction "1_1") (pintype "passive"))
      (node (ref "SERIAL2") (pin "2") (pinfunction "2_2") (pintype "passive"))
    )
    (net (code "219") (name "Net-(R1-Pad2)") (class "Default")
      (node (ref "R1") (pin "2") (pinfunction "2_2") (pintype "passive"))
      (node (ref "U1") (pin "48") (pinfunction "48_48") (pintype "bidirectional"))
    )
    (net (code "220") (name "Net-(R2-Pad2)") (class "Default")
      (node (ref "R2") (pin "2") (pinfunction "2_2") (pintype "passive"))
      (node (ref "U1") (pin "49") (pinfunction "49_49") (pintype "bidirectional"))
    )
    (net (code "221") (name "Net-(R56-Pad2)") (class "Default")
      (node (ref "R56") (pin "2") (pinfunction "2_2") (pintype "passive"))
      (node (ref "R58") (pin "1") (pinfunction "1_1") (pintype "passive"))
      (node (ref "SW1") (pin "B") (pinfunction "B_B") (pintype "passive"))
      (node (ref "U$66") (pin "2") (pinfunction "2_2") (pintype "passive"))
    )
    (net (code "222") (name "Net-(SJ1-Pad1)") (class "Default")
      (node (ref "SJ1") (pin "1") (pinfunction "1_1") (pintype "passive"))
      (node (ref "UART1") (pin "10") (pinfunction "10_10") (pintype "passive"))
    )
    (net (code "223") (name "Net-(SJ2-Pad2)") (class "Default")
      (node (ref "SJ2") (pin "2") (pinfunction "2_2") (pintype "passive"))
      (node (ref "UART1") (pin "9") (pinfunction "9_9") (pintype "passive"))
    )
    (net (code "224") (name "Net-(U$1-P$2)") (class "Default")
      (node (ref "R8") (pin "1") (pinfunction "1_1") (pintype "passive"))
      (node (ref "U$1") (pin "A2") (pinfunction "P$2_A2") (pintype "bidirectional"))
    )
    (net (code "225") (name "Net-(U$1-P$3)") (class "Default")
      (node (ref "R7") (pin "1") (pinfunction "1_1") (pintype "passive"))
      (node (ref "U$1") (pin "A3") (pinfunction "P$3_A3") (pintype "bidirectional"))
    )
    (net (code "226") (name "RESET") (class "Default")
      (node (ref "RESET") (pin "3") (pinfunction "3_3") (pintype "passive"))
      (node (ref "RESETA") (pin "3") (pinfunction "3_3") (pintype "passive"))
      (node (ref "U1") (pin "RESET") (pinfunction "RESET_RESET") (pintype "bidirectional"))
    )
    (net (code "227") (name "RXD1") (class "Default")
      (node (ref "U1") (pin "19") (pinfunction "19(RX1)_19") (pintype "bidirectional"))
      (node (ref "UART1") (pin "2") (pinfunction "2_2") (pintype "passive"))
    )
    (net (code "228") (name "RXD2") (class "Default")
      (node (ref "U1") (pin "17") (pinfunction "17(RX2)_17") (pintype "bidirectional"))
    )
    (net (code "229") (name "RXD3") (class "Default")
      (node (ref "U1") (pin "15") (pinfunction "15(RX3)_15") (pintype "bidirectional"))
    )
    (net (code "230") (name "SCLK") (class "Default")
      (node (ref "C1") (pin "1") (pinfunction "1_1") (pintype "passive"))
      (node (ref "R1") (pin "1") (pinfunction "1_1") (pintype "passive"))
      (node (ref "SERIAL1") (pin "7") (pinfunction "7_7") (pintype "passive"))
      (node (ref "SERIAL2") (pin "7") (pinfunction "7_7") (pintype "passive"))
      (node (ref "SERIAL3") (pin "7") (pinfunction "7_7") (pintype "passive"))
      (node (ref "SSW1") (pin "7") (pinfunction "SCK_7") (pintype "bidirectional"))
      (node (ref "SSW2") (pin "7") (pinfunction "SCK_7") (pintype "bidirectional"))
    )
    (net (code "231") (name "SW1") (class "Default")
      (node (ref "JOYSTICKS") (pin "1") (pinfunction "1_1") (pintype "passive"))
      (node (ref "U1") (pin "35") (pinfunction "35_35") (pintype "bidirectional"))
    )
    (net (code "232") (name "SW2") (class "Default")
      (node (ref "JOYSTICKS") (pin "4") (pinfunction "4_4") (pintype "passive"))
      (node (ref "U1") (pin "36") (pinfunction "36_36") (pintype "bidirectional"))
    )
    (net (code "233") (name "TXD1") (class "Default")
      (node (ref "U1") (pin "18") (pinfunction "18(TX1)_18") (pintype "bidirectional"))
      (node (ref "UART1") (pin "3") (pinfunction "3_3") (pintype "passive"))
    )
    (net (code "234") (name "TXD2") (class "Default")
      (node (ref "U1") (pin "16") (pinfunction "16(TX2)_16") (pintype "bidirectional"))
    )
    (net (code "235") (name "TXD3") (class "Default")
      (node (ref "U1") (pin "14") (pinfunction "14(TX3)_14") (pintype "bidirectional"))
    )
    (net (code "236") (name "VIN") (class "Default")
      (node (ref "U1") (pin "VIN") (pinfunction "VIN_VIN") (pintype "bidirectional"))
    )
    (net (code "237") (name "unconnected-(IC1-INTA-Pad20)") (class "Default")
      (node (ref "IC1") (pin "20") (pinfunction "INTA_20") (pintype "output"))
    )
    (net (code "238") (name "unconnected-(IC1-INTB-Pad19)") (class "Default")
      (node (ref "IC1") (pin "19") (pinfunction "INTB_19") (pintype "output"))
    )
    (net (code "239") (name "unconnected-(IC5-L12-Pad19)") (class "Default")
      (node (ref "IC5") (pin "19") (pinfunction "L12_19") (pintype "output"))
    )
    (net (code "240") (name "unconnected-(IC5-L13-Pad20)") (class "Default")
      (node (ref "IC5") (pin "20") (pinfunction "L13_20") (pintype "output"))
    )
    (net (code "241") (name "unconnected-(IC5-L14-Pad21)") (class "Default")
      (node (ref "IC5") (pin "21") (pinfunction "L14_21") (pintype "output"))
    )
    (net (code "242") (name "unconnected-(IC5-L15-Pad22)") (class "Default")
      (node (ref "IC5") (pin "22") (pinfunction "L15_22") (pintype "output"))
    )
    (net (code "243") (name "unconnected-(IC6-INTA-Pad20)") (class "Default")
      (node (ref "IC6") (pin "20") (pinfunction "INTA_20") (pintype "output"))
    )
    (net (code "244") (name "unconnected-(IC6-INTB-Pad19)") (class "Default")
      (node (ref "IC6") (pin "19") (pinfunction "INTB_19") (pintype "output"))
    )
    (net (code "245") (name "unconnected-(IC7-GPA2-Pad23)") (class "Default")
      (node (ref "IC7") (pin "23") (pinfunction "GPA2_23") (pintype "bidirectional"))
    )
    (net (code "246") (name "unconnected-(IC7-GPA3-Pad24)") (class "Default")
      (node (ref "IC7") (pin "24") (pinfunction "GPA3_24") (pintype "bidirectional"))
    )
    (net (code "247") (name "unconnected-(IC7-GPA4-Pad25)") (class "Default")
      (node (ref "IC7") (pin "25") (pinfunction "GPA4_25") (pintype "bidirectional"))
    )
    (net (code "248") (name "unconnected-(IC7-GPA5-Pad26)") (class "Default")
      (node (ref "IC7") (pin "26") (pinfunction "GPA5_26") (pintype "bidirectional"))
    )
    (net (code "249") (name "unconnected-(IC7-GPA6-Pad27)") (class "Default")
      (node (ref "IC7") (pin "27") (pinfunction "GPA6_27") (pintype "bidirectional"))
    )
    (net (code "250") (name "unconnected-(IC7-GPA7-Pad28)") (class "Default")
      (node (ref "IC7") (pin "28") (pinfunction "GPA7_28") (pintype "bidirectional"))
    )
    (net (code "251") (name "unconnected-(IC7-GPB2-Pad3)") (class "Default")
      (node (ref "IC7") (pin "3") (pinfunction "GPB2_3") (pintype "bidirectional"))
    )
    (net (code "252") (name "unconnected-(IC7-GPB3-Pad4)") (class "Default")
      (node (ref "IC7") (pin "4") (pinfunction "GPB3_4") (pintype "bidirectional"))
    )
    (net (code "253") (name "unconnected-(IC7-GPB4-Pad5)") (class "Default")
      (node (ref "IC7") (pin "5") (pinfunction "GPB4_5") (pintype "bidirectional"))
    )
    (net (code "254") (name "unconnected-(IC7-GPB5-Pad6)") (class "Default")
      (node (ref "IC7") (pin "6") (pinfunction "GPB5_6") (pintype "bidirectional"))
    )
    (net (code "255") (name "unconnected-(IC7-GPB6-Pad7)") (class "Default")
      (node (ref "IC7") (pin "7") (pinfunction "GPB6_7") (pintype "bidirectional"))
    )
    (net (code "256") (name "unconnected-(IC7-GPB7-Pad8)") (class "Default")
      (node (ref "IC7") (pin "8") (pinfunction "GPB7_8") (pintype "bidirectional"))
    )
    (net (code "257") (name "unconnected-(IC7-INTA-Pad20)") (class "Default")
      (node (ref "IC7") (pin "20") (pinfunction "INTA_20") (pintype "output"))
    )
    (net (code "258") (name "unconnected-(IC7-INTB-Pad19)") (class "Default")
      (node (ref "IC7") (pin "19") (pinfunction "INTB_19") (pintype "output"))
    )
    (net (code "259") (name "unconnected-(IC8-GPA2-Pad23)") (class "Default")
      (node (ref "IC8") (pin "23") (pinfunction "GPA2_23") (pintype "bidirectional"))
    )
    (net (code "260") (name "unconnected-(IC8-GPA3-Pad24)") (class "Default")
      (node (ref "IC8") (pin "24") (pinfunction "GPA3_24") (pintype "bidirectional"))
    )
    (net (code "261") (name "unconnected-(IC8-GPA4-Pad25)") (class "Default")
      (node (ref "IC8") (pin "25") (pinfunction "GPA4_25") (pintype "bidirectional"))
    )
    (net (code "262") (name "unconnected-(IC8-GPA5-Pad26)") (class "Default")
      (node (ref "IC8") (pin "26") (pinfunction "GPA5_26") (pintype "bidirectional"))
    )
    (net (code "263") (name "unconnected-(IC8-GPA6-Pad27)") (class "Default")
      (node (ref "IC8") (pin "27") (pinfunction "GPA6_27") (pintype "bidirectional"))
    )
    (net (code "264") (name "unconnected-(IC8-GPA7-Pad28)") (class "Default")
      (node (ref "IC8") (pin "28") (pinfunction "GPA7_28") (pintype "bidirectional"))
    )
    (net (code "265") (name "unconnected-(IC8-GPB1-Pad2)") (class "Default")
      (node (ref "IC8") (pin "2") (pinfunction "GPB1_2") (pintype "bidirectional"))
    )
    (net (code "266") (name "unconnected-(IC8-GPB2-Pad3)") (class "Default")
      (node (ref "IC8") (pin "3") (pinfunction "GPB2_3") (pintype "bidirectional"))
    )
    (net (code "267") (name "unconnected-(IC8-GPB3-Pad4)") (class "Default")
      (node (ref "IC8") (pin "4") (pinfunction "GPB3_4") (pintype "bidirectional"))
    )
    (net (code "268") (name "unconnected-(IC8-GPB4-Pad5)") (class "Default")
      (node (ref "IC8") (pin "5") (pinfunction "GPB4_5") (pintype "bidirectional"))
    )
    (net (code "269") (name "unconnected-(IC8-GPB5-Pad6)") (class "Default")
      (node (ref "IC8") (pin "6") (pinfunction "GPB5_6") (pintype "bidirectional"))
    )
    (net (code "270") (name "unconnected-(IC8-GPB6-Pad7)") (class "Default")
      (node (ref "IC8") (pin "7") (pinfunction "GPB6_7") (pintype "bidirectional"))
    )
    (net (code "271") (name "unconnected-(IC8-GPB7-Pad8)") (class "Default")
      (node (ref "IC8") (pin "8") (pinfunction "GPB7_8") (pintype "bidirectional"))
    )
    (net (code "272") (name "unconnected-(IC8-INTA-Pad20)") (class "Default")
      (node (ref "IC8") (pin "20") (pinfunction "INTA_20") (pintype "output"))
    )
    (net (code "273") (name "unconnected-(IC8-INTB-Pad19)") (class "Default")
      (node (ref "IC8") (pin "19") (pinfunction "INTB_19") (pintype "output"))
    )
    (net (code "274") (name "unconnected-(IC9B-O-Pad10)") (class "Default")
      (node (ref "IC9") (pin "10") (pinfunction "O_10") (pintype "output"))
    )
    (net (code "275") (name "unconnected-(IC9C-O-Pad8)") (class "Default")
      (node (ref "IC9") (pin "8") (pinfunction "O_8") (pintype "output"))
    )
    (net (code "276") (name "unconnected-(IC9D-O-Pad2)") (class "Default")
      (node (ref "IC9") (pin "2") (pinfunction "O_2") (pintype "output"))
    )
    (net (code "277") (name "unconnected-(IC9E-O-Pad4)") (class "Default")
      (node (ref "IC9") (pin "4") (pinfunction "O_4") (pintype "output"))
    )
    (net (code "278") (name "unconnected-(IC9F-O-Pad6)") (class "Default")
      (node (ref "IC9") (pin "6") (pinfunction "O_6") (pintype "output"))
    )
    (net (code "279") (name "unconnected-(JP1-Pad1)") (class "Default")
      (node (ref "JP1") (pin "1") (pinfunction "1_1") (pintype "passive"))
    )
    (net (code "280") (name "unconnected-(JP1-Pad2)") (class "Default")
      (node (ref "JP1") (pin "2") (pinfunction "2_2") (pintype "passive"))
    )
    (net (code "281") (name "unconnected-(JP2-Pad1)") (class "Default")
      (node (ref "JP2") (pin "1") (pinfunction "1_1") (pintype "passive"))
    )
    (net (code "282") (name "unconnected-(JP2-Pad2)") (class "Default")
      (node (ref "JP2") (pin "2") (pinfunction "2_2") (pintype "passive"))
    )
    (net (code "283") (name "unconnected-(SERIAL1-Pad6)") (class "Default")
      (node (ref "SERIAL1") (pin "6") (pinfunction "6_6") (pintype "passive"))
    )
    (net (code "284") (name "unconnected-(SERIAL2-Pad6)") (class "Default")
      (node (ref "SERIAL2") (pin "6") (pinfunction "6_6") (pintype "passive"))
    )
    (net (code "285") (name "unconnected-(SERIAL3-Pad6)") (class "Default")
      (node (ref "SERIAL3") (pin "6") (pinfunction "6_6") (pintype "passive"))
    )
    (net (code "286") (name "unconnected-(SSW1-SDO-Pad5)") (class "Default")
      (node (ref "SSW1") (pin "5") (pinfunction "SDO_5") (pintype "bidirectional"))
    )
    (net (code "287") (name "unconnected-(SSW2-SDO-Pad5)") (class "Default")
      (node (ref "SSW2") (pin "5") (pinfunction "SDO_5") (pintype "bidirectional"))
    )
    (net (code "288") (name "unconnected-(U$34-PadA1)") (class "Default")
      (node (ref "U$34") (pin "A1") (pinfunction "A1_A1") (pintype "passive"))
    )
    (net (code "289") (name "unconnected-(U1-0(RX0)-Pad0)") (class "Default")
      (node (ref "U1") (pin "0") (pinfunction "0(RX0)_0") (pintype "bidirectional"))
    )
    (net (code "290") (name "unconnected-(U1-1(TX0)-Pad1)") (class "Default")
      (node (ref "U1") (pin "1") (pinfunction "1(TX0)_1") (pintype "bidirectional"))
    )
    (net (code "291") (name "unconnected-(U1-Pad2)") (class "Default")
      (node (ref "U1") (pin "2") (pinfunction "2_2") (pintype "bidirectional"))
    )
    (net (code "292") (name "unconnected-(U1-Pad3)") (class "Default")
      (node (ref "U1") (pin "3") (pinfunction "3_3") (pintype "bidirectional"))
    )
    (net (code "293") (name "unconnected-(U1-Pad3.3V)") (class "Default")
      (node (ref "U1") (pin "3.3V") (pinfunction "3.3V_3.3V") (pintype "bidirectional"))
    )
    (net (code "294") (name "unconnected-(U1-Pad4)") (class "Default")
      (node (ref "U1") (pin "4") (pinfunction "4_4") (pintype "bidirectional"))
    )
    (net (code "295") (name "unconnected-(U1-Pad5)") (class "Default")
      (node (ref "U1") (pin "5") (pinfunction "5_5") (pintype "bidirectional"))
    )
    (net (code "296") (name "unconnected-(U1-Pad10)") (class "Default")
      (node (ref "U1") (pin "10") (pinfunction "10_10") (pintype "bidirectional"))
    )
    (net (code "297") (name "unconnected-(U1-Pad11)") (class "Default")
      (node (ref "U1") (pin "11") (pinfunction "11_11") (pintype "bidirectional"))
    )
    (net (code "298") (name "unconnected-(U1-Pad12)") (class "Default")
      (node (ref "U1") (pin "12") (pinfunction "12_12") (pintype "bidirectional"))
    )
    (net (code "299") (name "unconnected-(U1-Pad13)") (class "Default")
      (node (ref "U1") (pin "13") (pinfunction "13_13") (pintype "bidirectional"))
    )
    (net (code "300") (name "unconnected-(U1-PadAREF)") (class "Default")
      (node (ref "U1") (pin "AREF") (pinfunction "AREF_AREF") (pintype "bidirectional"))
    )
    (net (code "301") (name "unconnected-(UART1-Pad1)") (class "Default")
      (node (ref "UART1") (pin "1") (pinfunction "1_1") (pintype "passive"))
    )
    (net (code "302") (name "unconnected-(UART1-Pad4)") (class "Default")
      (node (ref "UART1") (pin "4") (pinfunction "4_4") (pintype "passive"))
    )
    (net (code "303") (name "unconnected-(UART1-Pad6)") (class "Default")
      (node (ref "UART1") (pin "6") (pinfunction "6_6") (pintype "passive"))
    )
    (net (code "304") (name "unconnected-(UART1-Pad7)") (class "Default")
      (node (ref "UART1") (pin "7") (pinfunction "7_7") (pintype "passive"))
    )
    (net (code "305") (name "unconnected-(UART1-Pad8)") (class "Default")
      (node (ref "UART1") (pin "8") (pinfunction "8_8") (pintype "passive"))
    )
  )
)
